# EEZ_XMOS_eval_r1B5.net
KiCad netlist of a schematic drawn in EAGLE
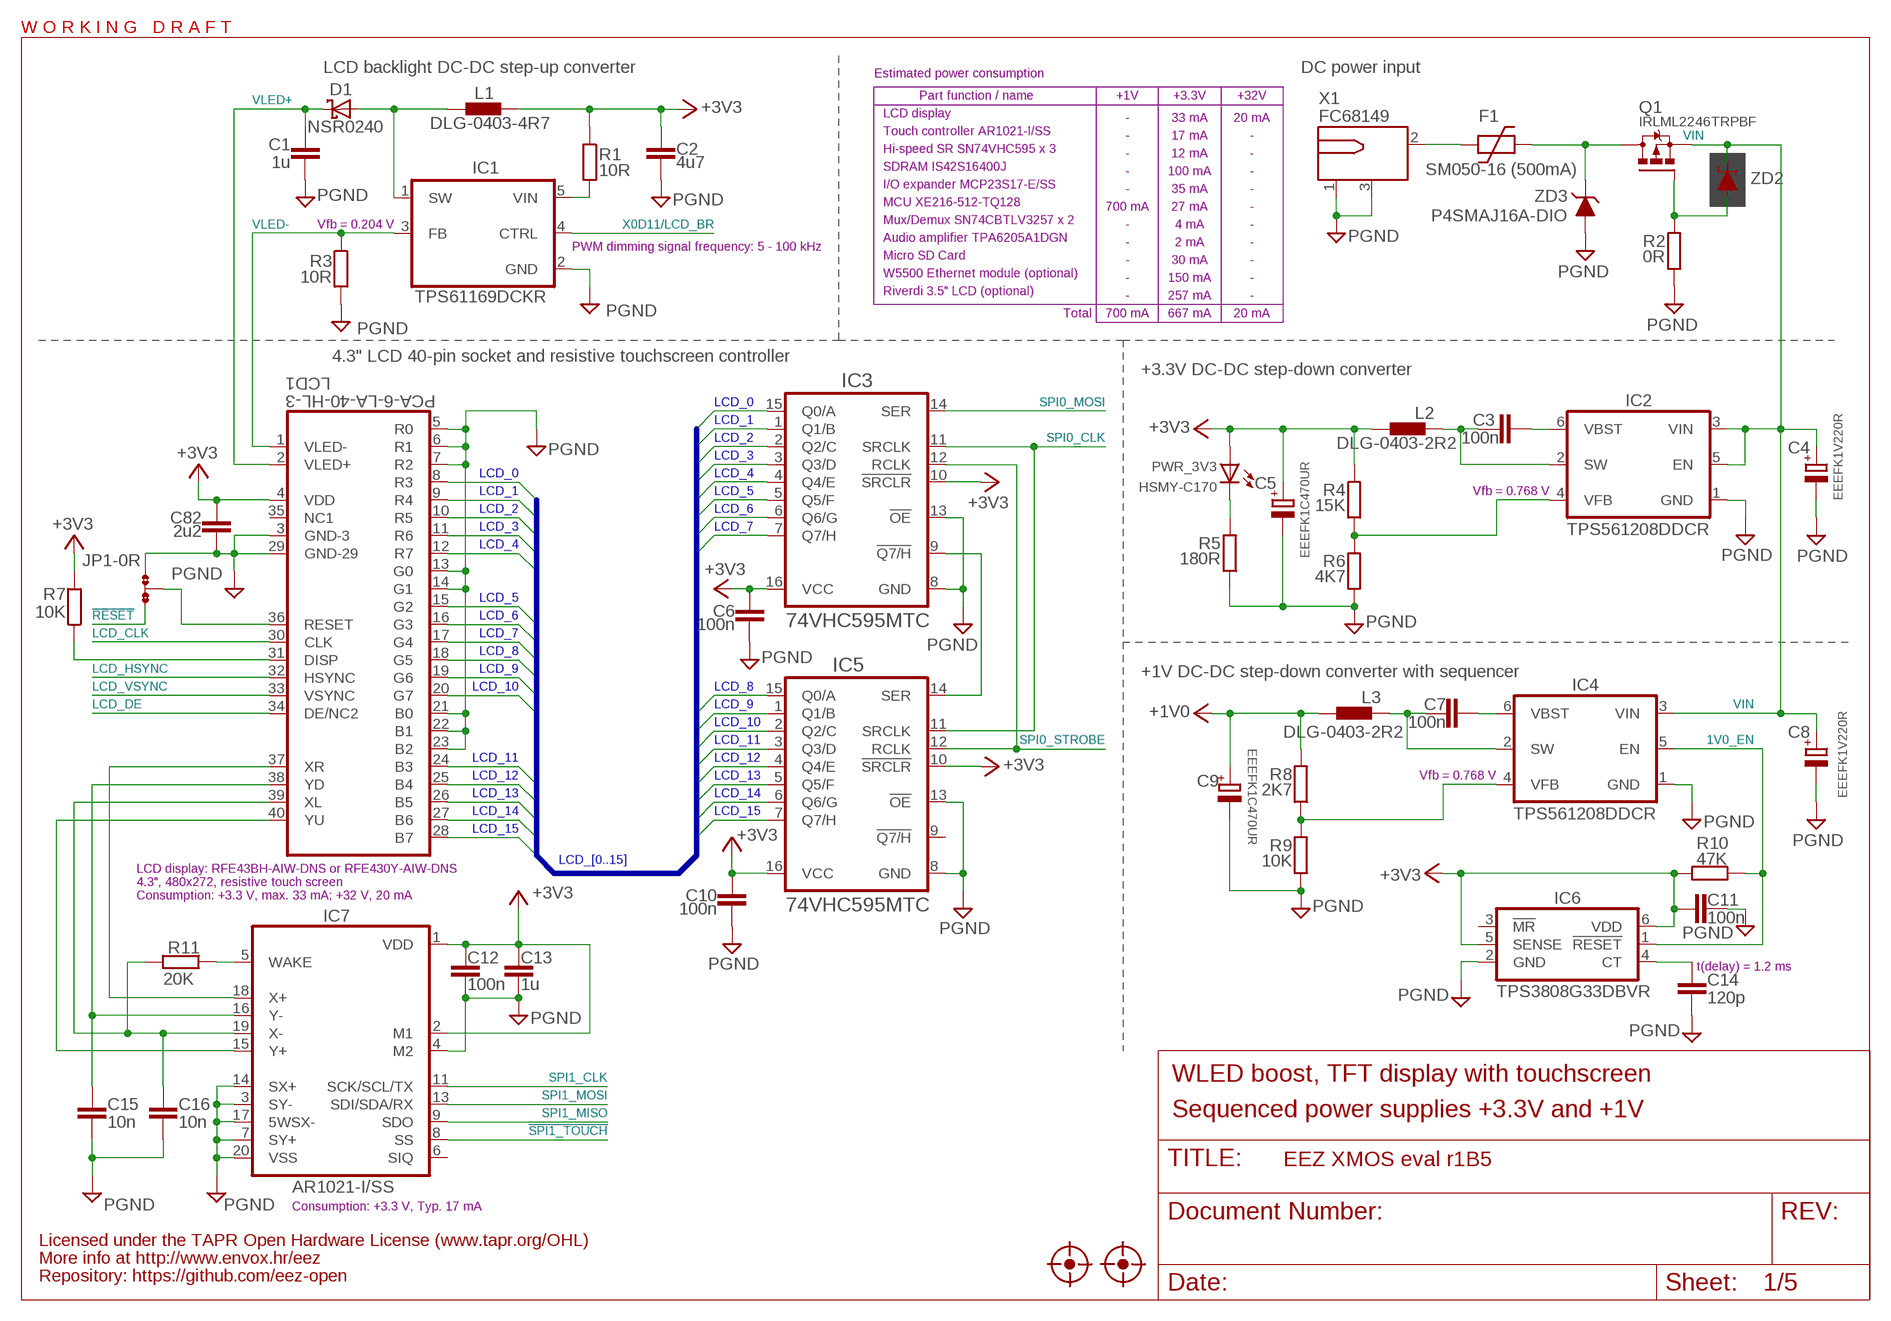
[diagram p0: schematic, sheet 1]
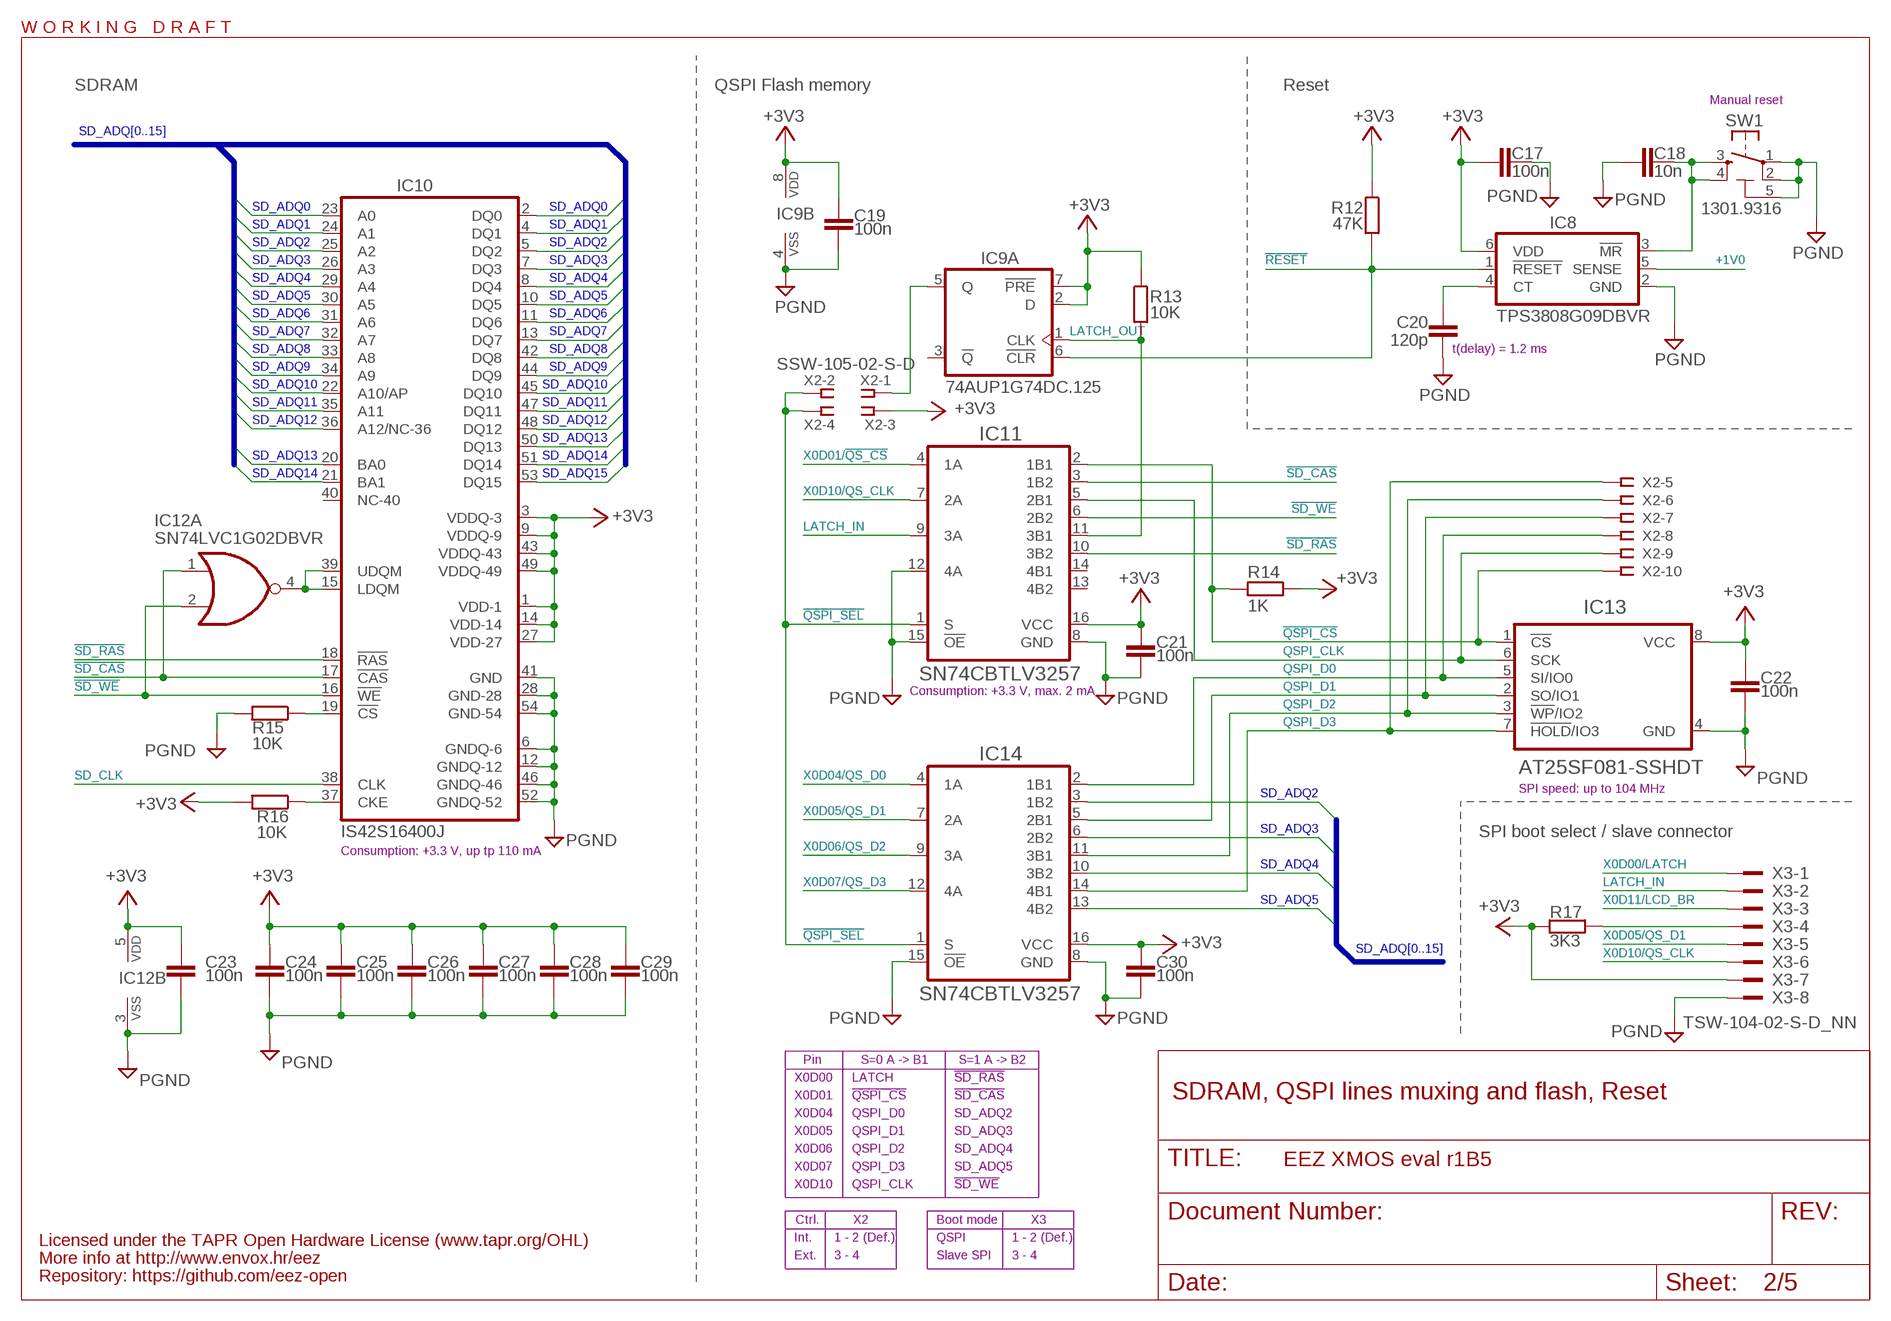
[diagram p1: schematic, sheet 2]
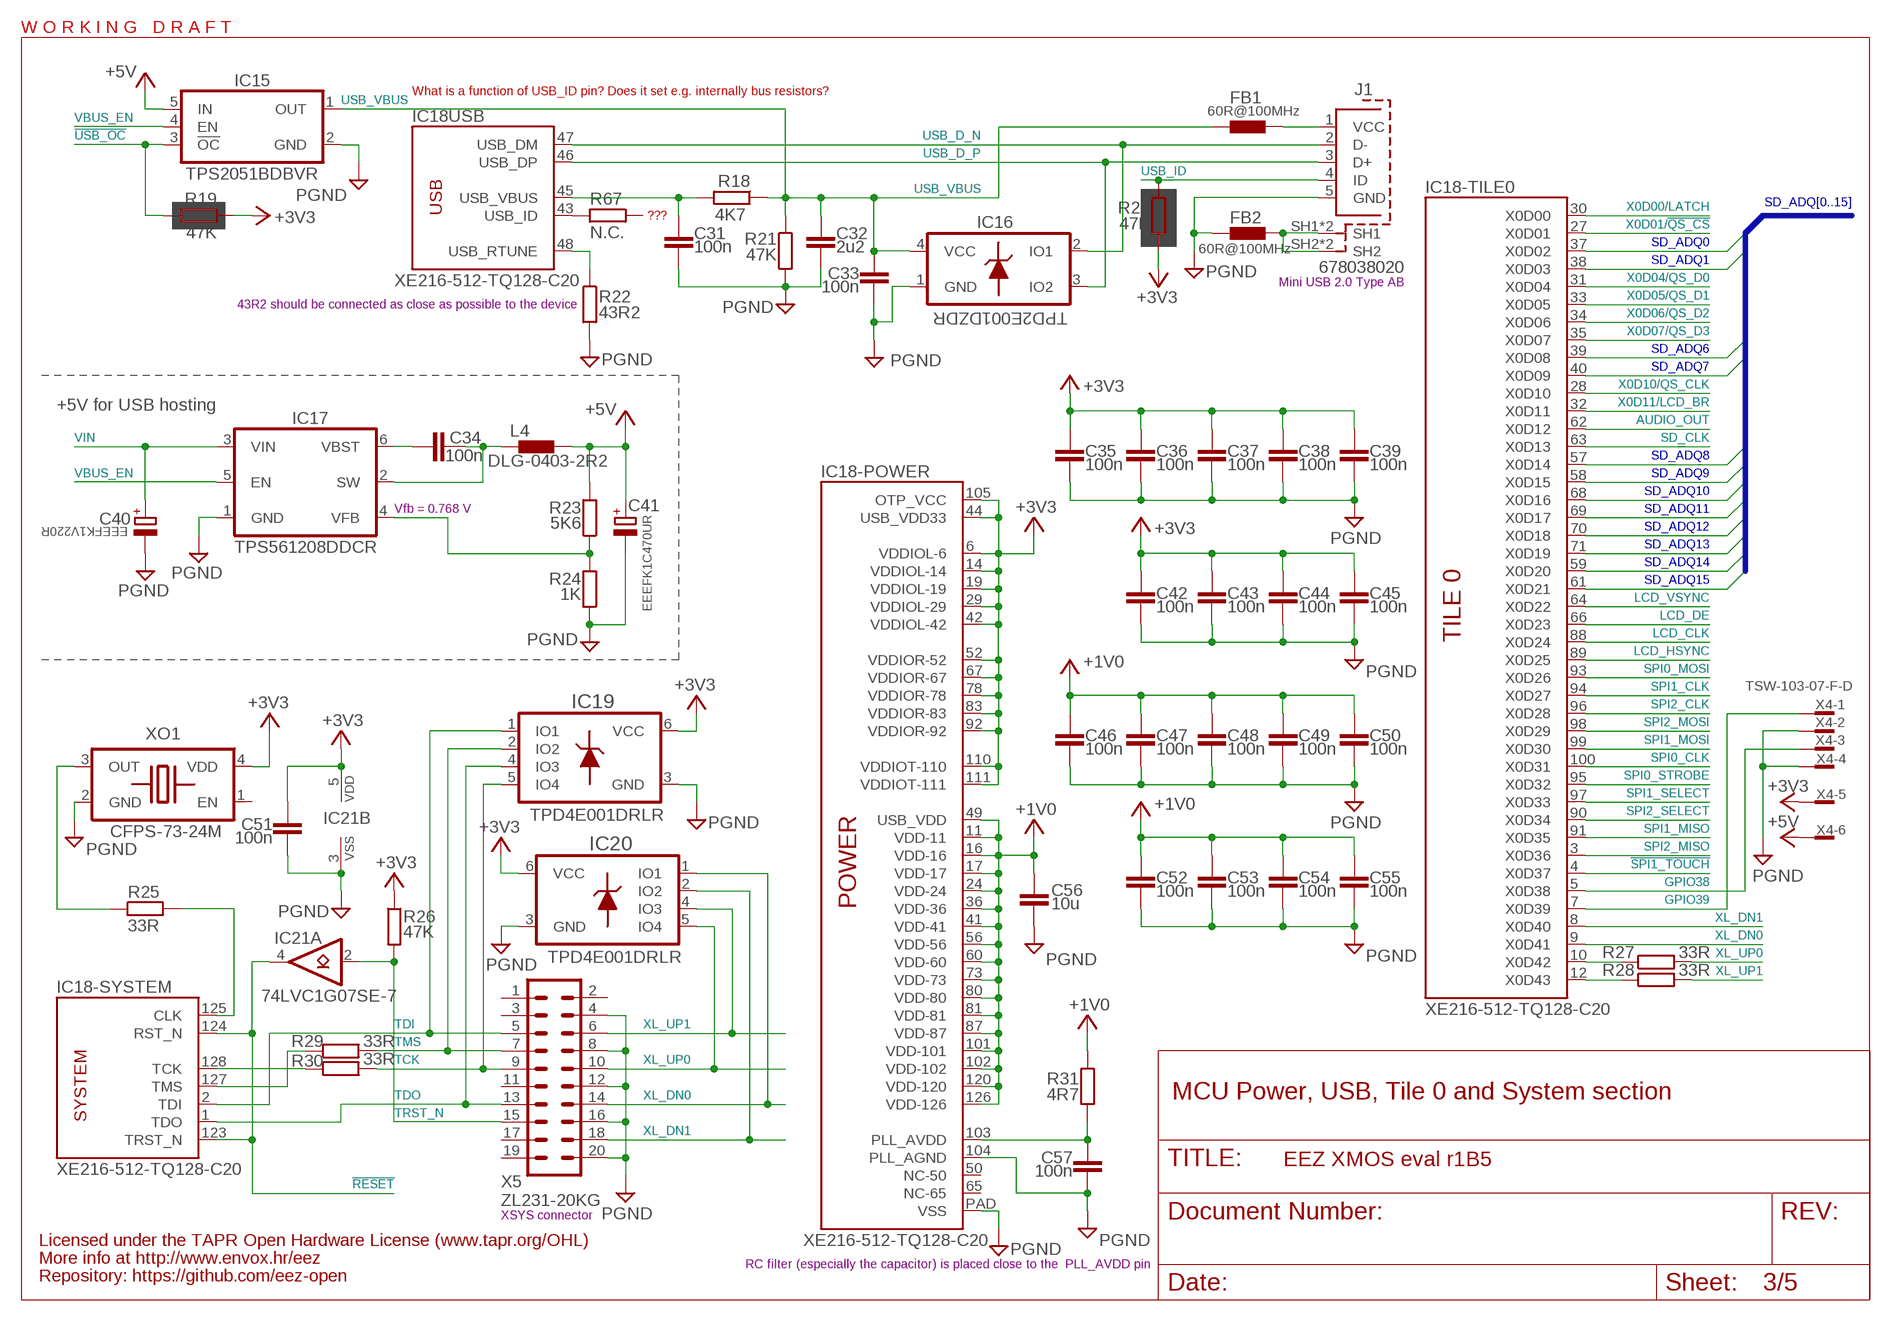
[diagram p2: schematic, sheet 3]
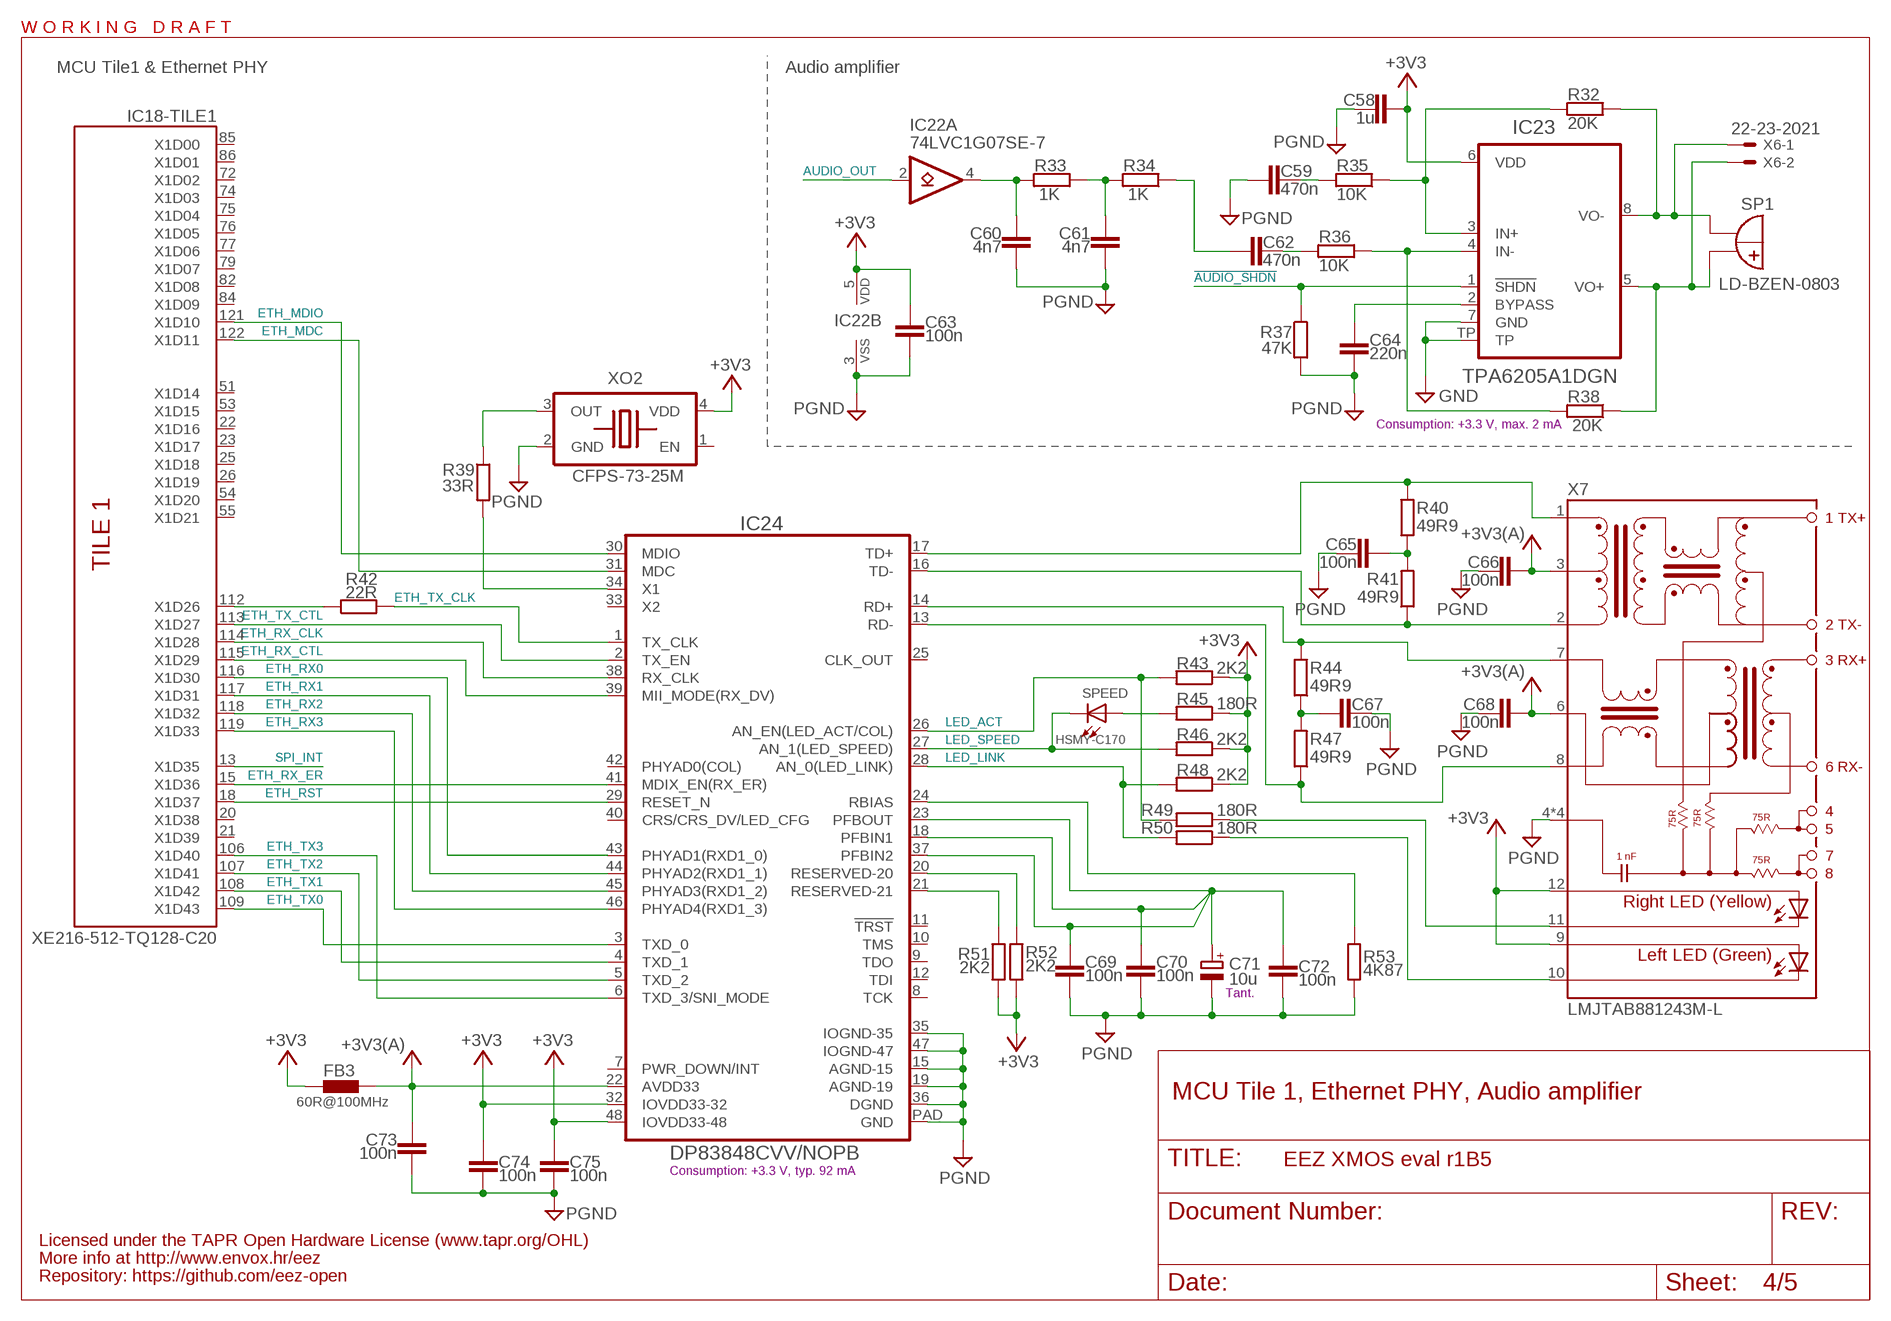
[diagram p3: schematic, sheet 4]
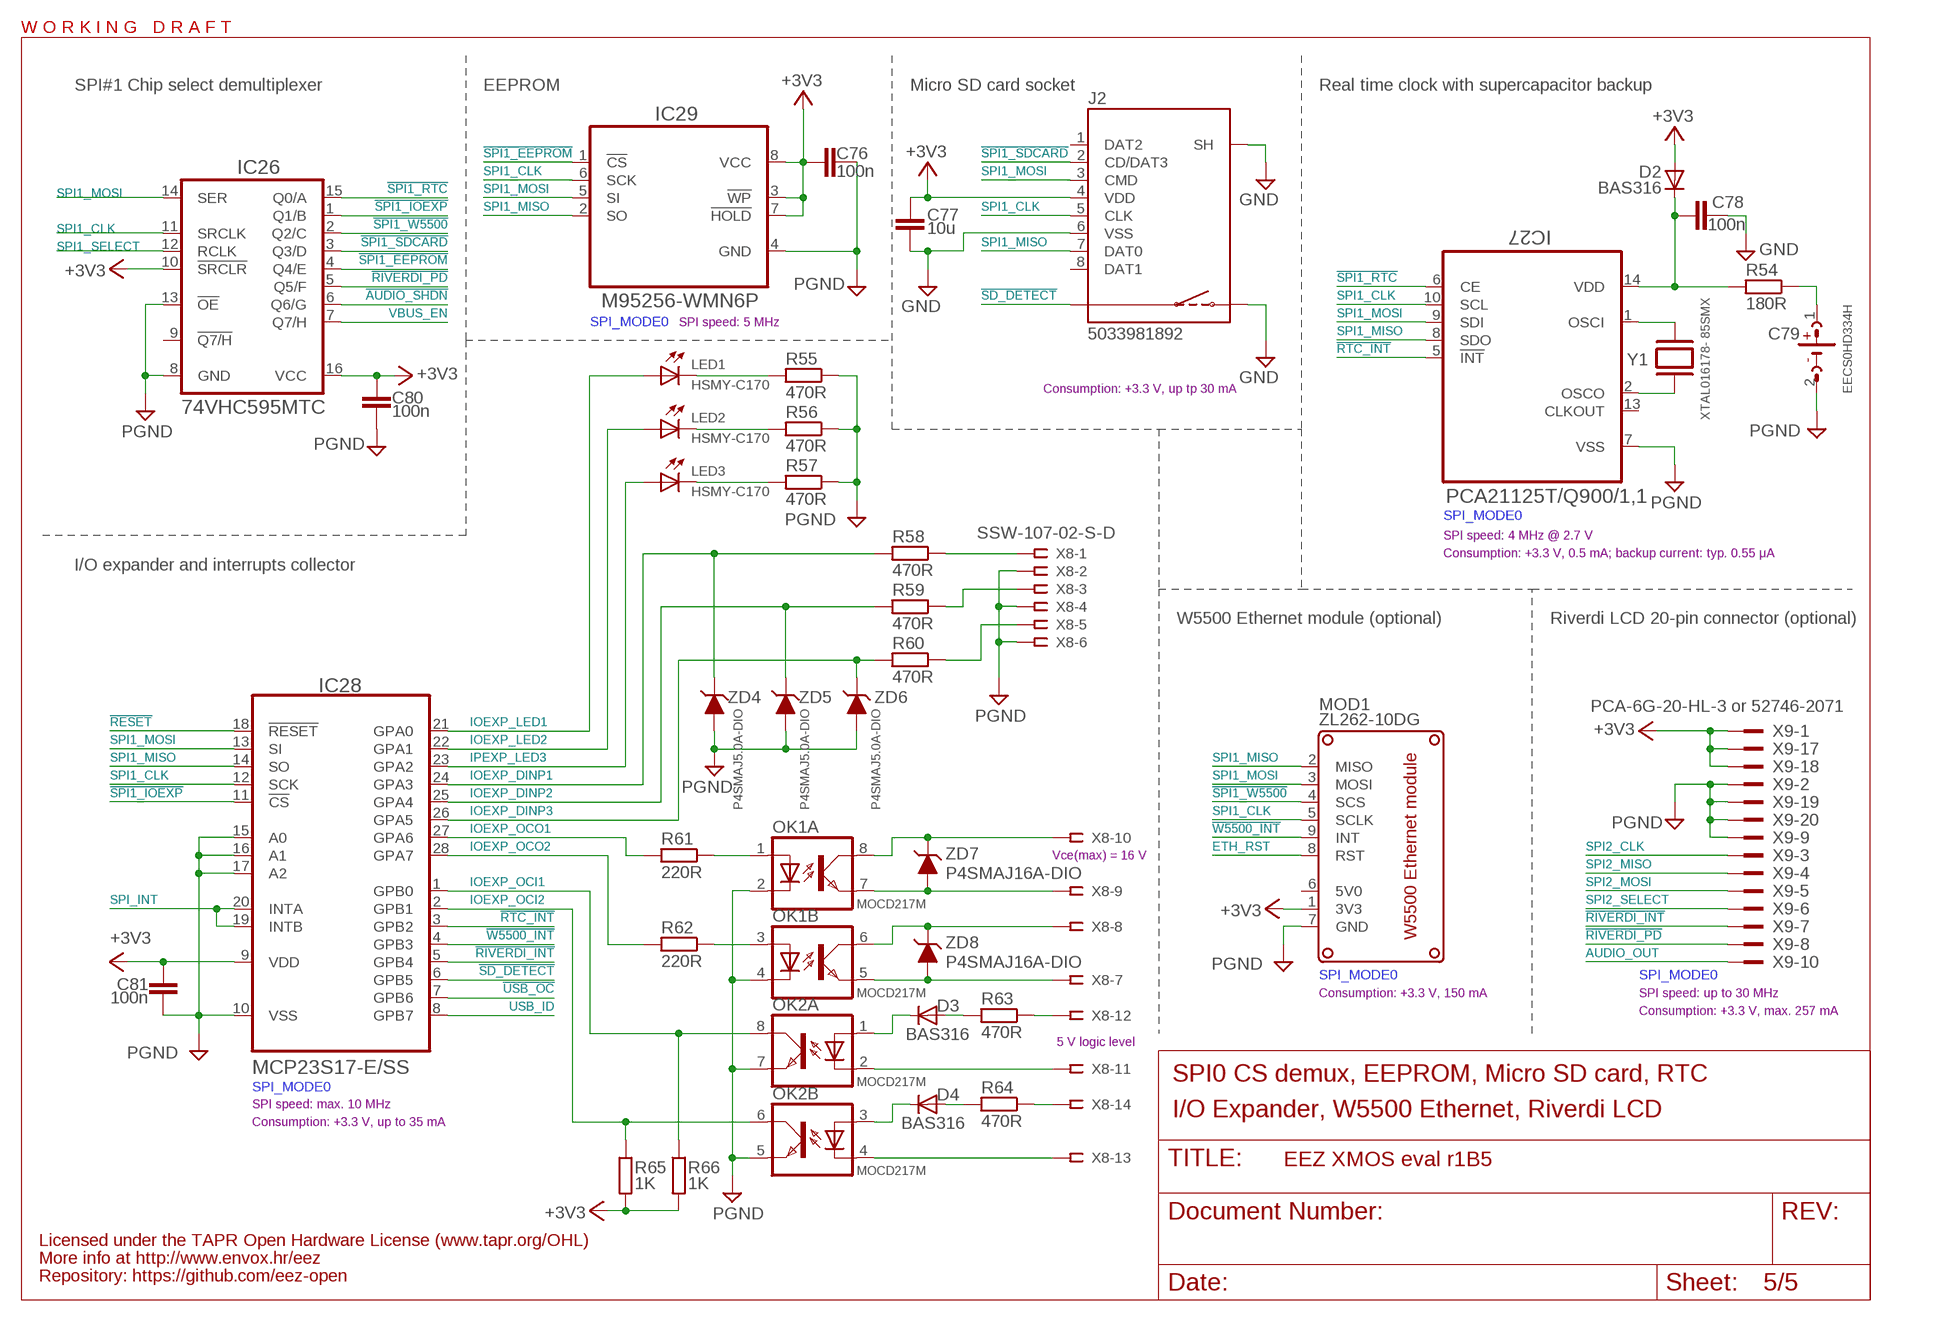
[diagram p4: schematic, sheet 5]

(export (version "E")
  (design (tool "Eeschema 10.0.6"))
  (components
    (comp (ref "C31")
      (value "100n")
      (footprint "eagle-import:C0603")
      (libsource (lib "eagle-import") (part "C-EUC0603"))
    )
    (comp (ref "C32")
      (value "2u2")
      (footprint "eagle-import:C0805")
      (libsource (lib "eagle-import") (part "C-EUC0805"))
    )
    (comp (ref "C33")
      (value "100n")
      (footprint "eagle-import:C0603")
      (libsource (lib "eagle-import") (part "C-EUC0603"))
    )
    (comp (ref "C34")
      (value "100n")
      (footprint "eagle-import:C0603")
      (libsource (lib "eagle-import") (part "C-EUC0603"))
    )
    (comp (ref "C35")
      (value "100n")
      (footprint "eagle-import:C0603")
      (libsource (lib "eagle-import") (part "C-EUC0603"))
    )
    (comp (ref "C36")
      (value "100n")
      (footprint "eagle-import:C0603")
      (libsource (lib "eagle-import") (part "C-EUC0603"))
    )
    (comp (ref "C37")
      (value "100n")
      (footprint "eagle-import:C0603")
      (libsource (lib "eagle-import") (part "C-EUC0603"))
    )
    (comp (ref "C38")
      (value "100n")
      (footprint "eagle-import:C0603")
      (libsource (lib "eagle-import") (part "C-EUC0603"))
    )
    (comp (ref "C39")
      (value "100n")
      (footprint "eagle-import:C0603")
      (libsource (lib "eagle-import") (part "C-EUC0603"))
    )
    (comp (ref "C40")
      (value "EEEFK1V220R")
      (footprint "eagle-import:CAPAE530X610N")
      (fields (field (name "MPN") "EEE-FK1V100R") (field (name "TOLERANCE") "±20 %"))
      (libsource (lib "eagle-import") (part "EEE--CASE-CFK1V100R"))
    )
    (comp (ref "C41")
      (value "EEEFK1C470UR")
      (footprint "eagle-import:CAPAE530X610N")
      (fields
        (field (name "MPN") "EEE-FK1V100R")
        (field (name "TOLERANCE") "±20 %")
        (field (name "MPN_1") "EEE-FK1V100R")
        (field (name "OC_FARNELL") "1850112  ")
        (field (name "OC_NEWARK") "23T0867")
        (field (name "PACKAGE") "CASE-C")
        (field (name "SUPPLIER") "PANASONIC")
        (field (name "TOLERANCE_1") "±20 %")
        (field (name "VOLTAGERATING") "35V")
      )
      (libsource (lib "eagle-import") (part "EEE--CASE-CFK1V100R"))
    )
    (comp (ref "C42")
      (value "100n")
      (footprint "eagle-import:C0603")
      (libsource (lib "eagle-import") (part "C-EUC0603"))
    )
    (comp (ref "C43")
      (value "100n")
      (footprint "eagle-import:C0603")
      (libsource (lib "eagle-import") (part "C-EUC0603"))
    )
    (comp (ref "C44")
      (value "100n")
      (footprint "eagle-import:C0603")
      (libsource (lib "eagle-import") (part "C-EUC0603"))
    )
    (comp (ref "C45")
      (value "100n")
      (footprint "eagle-import:C0603")
      (libsource (lib "eagle-import") (part "C-EUC0603"))
    )
    (comp (ref "C46")
      (value "100n")
      (footprint "eagle-import:C0603")
      (libsource (lib "eagle-import") (part "C-EUC0603"))
    )
    (comp (ref "C47")
      (value "100n")
      (footprint "eagle-import:C0603")
      (libsource (lib "eagle-import") (part "C-EUC0603"))
    )
    (comp (ref "C48")
      (value "100n")
      (footprint "eagle-import:C0603")
      (libsource (lib "eagle-import") (part "C-EUC0603"))
    )
    (comp (ref "C49")
      (value "100n")
      (footprint "eagle-import:C0603")
      (libsource (lib "eagle-import") (part "C-EUC0603"))
    )
    (comp (ref "C50")
      (value "100n")
      (footprint "eagle-import:C0603")
      (libsource (lib "eagle-import") (part "C-EUC0603"))
    )
    (comp (ref "C51")
      (value "100n")
      (footprint "eagle-import:C0603")
      (libsource (lib "eagle-import") (part "C-EUC0603"))
    )
    (comp (ref "C52")
      (value "100n")
      (footprint "eagle-import:C0603")
      (libsource (lib "eagle-import") (part "C-EUC0603"))
    )
    (comp (ref "C53")
      (value "100n")
      (footprint "eagle-import:C0603")
      (libsource (lib "eagle-import") (part "C-EUC0603"))
    )
    (comp (ref "C54")
      (value "100n")
      (footprint "eagle-import:C0603")
      (libsource (lib "eagle-import") (part "C-EUC0603"))
    )
    (comp (ref "C55")
      (value "100n")
      (footprint "eagle-import:C0603")
      (libsource (lib "eagle-import") (part "C-EUC0603"))
    )
    (comp (ref "C56")
      (value "10u")
      (footprint "eagle-import:C1210")
      (libsource (lib "eagle-import") (part "C-EUC1210"))
    )
    (comp (ref "C57")
      (value "100n")
      (footprint "eagle-import:C0603")
      (libsource (lib "eagle-import") (part "C-EUC0603"))
    )
    (comp (ref "FB1")
      (value "60R@100MHz")
      (footprint "eagle-import:BEAD0603")
      (libsource (lib "eagle-import") (part "FERRITE_BEAD0603"))
    )
    (comp (ref "FB2")
      (value "60R@100MHz")
      (footprint "eagle-import:BEAD0603")
      (libsource (lib "eagle-import") (part "FERRITE_BEAD0603"))
    )
    (comp (ref "IC15")
      (value "TPS2051BDBVR")
      (footprint "eagle-import:DBV5")
      (libsource (lib "eagle-import") (part "TPS2051B"))
    )
    (comp (ref "IC16")
      (value "TPD2E001DZDR")
      (footprint "eagle-import:SOP192P292X122-4N")
      (libsource (lib "eagle-import") (part "TPD2E001DZDR"))
    )
    (comp (ref "IC17")
      (value "TPS561208DDCR")
      (footprint "eagle-import:DBV6")
      (libsource (lib "eagle-import") (part "TPS56120X"))
    )
    (comp (ref "IC18")
      (value "XE216-512-TQ128-C20")
      (footprint "eagle-import:TQ128")
      (libsource (lib "eagle-import") (part "XE216-TQ128"))
    )
    (comp (ref "IC19")
      (value "TPD4E001DRLR")
      (footprint "eagle-import:DRL6")
      (libsource (lib "eagle-import") (part "TPD4E001-DRL"))
    )
    (comp (ref "IC20")
      (value "TPD4E001DRLR")
      (footprint "eagle-import:DRL6")
      (libsource (lib "eagle-import") (part "TPD4E001-DRL"))
    )
    (comp (ref "IC21")
      (value "74LVC1G07SE-7")
      (footprint "eagle-import:DCK5")
      (libsource (lib "eagle-import") (part "SN74LVC1G07-SC70"))
    )
    (comp (ref "J1")
      (value "678038020")
      (footprint "eagle-import:678038020")
      (libsource (lib "eagle-import") (part "678038020"))
    )
    (comp (ref "L4")
      (value "DLG-0403-2R2")
      (footprint "eagle-import:DE0403")
      (libsource (lib "eagle-import") (part "DE0403"))
    )
    (comp (ref "R18")
      (value "4K7")
      (footprint "eagle-import:R0805")
      (libsource (lib "eagle-import") (part "R-EU_R0805"))
    )
    (comp (ref "R19")
      (value "47K")
      (footprint "eagle-import:R0805")
      (libsource (lib "eagle-import") (part "R-EU_R0805"))
    )
    (comp (ref "R20")
      (value "47K")
      (footprint "eagle-import:R0805")
      (libsource (lib "eagle-import") (part "R-EU_R0805"))
    )
    (comp (ref "R21")
      (value "47K")
      (footprint "eagle-import:R0805")
      (libsource (lib "eagle-import") (part "R-EU_R0805"))
    )
    (comp (ref "R22")
      (value "43R2")
      (footprint "eagle-import:R0805")
      (libsource (lib "eagle-import") (part "R-EU_R0805"))
    )
    (comp (ref "R23")
      (value "5K6")
      (footprint "eagle-import:R0805")
      (libsource (lib "eagle-import") (part "R-EU_R0805"))
    )
    (comp (ref "R24")
      (value "1K")
      (footprint "eagle-import:R0805")
      (libsource (lib "eagle-import") (part "R-EU_R0805"))
    )
    (comp (ref "R25")
      (value "33R")
      (footprint "eagle-import:R0603")
      (libsource (lib "eagle-import") (part "R-EU_R0603"))
    )
    (comp (ref "R26")
      (value "47K")
      (footprint "eagle-import:R0805")
      (libsource (lib "eagle-import") (part "R-EU_R0805"))
    )
    (comp (ref "R27")
      (value "33R")
      (footprint "eagle-import:R0603")
      (libsource (lib "eagle-import") (part "R-EU_R0603"))
    )
    (comp (ref "R28")
      (value "33R")
      (footprint "eagle-import:R0603")
      (libsource (lib "eagle-import") (part "R-EU_R0603"))
    )
    (comp (ref "R29")
      (value "33R")
      (footprint "eagle-import:R0603")
      (libsource (lib "eagle-import") (part "R-EU_R0603"))
    )
    (comp (ref "R30")
      (value "33R")
      (footprint "eagle-import:R0603")
      (libsource (lib "eagle-import") (part "R-EU_R0603"))
    )
    (comp (ref "R31")
      (value "4R7")
      (footprint "eagle-import:R0805")
      (libsource (lib "eagle-import") (part "R-EU_R0805"))
    )
    (comp (ref "R67")
      (value "N.C.")
      (footprint "eagle-import:R0805")
      (libsource (lib "eagle-import") (part "R-EU_R0805"))
    )
    (comp (ref "X4")
      (value "TSW-103-07-F-D")
      (footprint "eagle-import:TSW-103-07-F-D")
      (libsource (lib "eagle-import") (part "TSW-103-07-F-D"))
    )
    (comp (ref "X5")
      (value "ZL231-20KG")
      (footprint "eagle-import:ML20L")
      (libsource (lib "eagle-import") (part "ML20L"))
    )
    (comp (ref "XO1")
      (value "CFPS-73-24M")
      (footprint "eagle-import:12SMX(C)")
      (libsource (lib "eagle-import") (part "XO-7X5MM"))
    )
    (comp (ref "C76")
      (value "100n")
      (footprint "eagle-import:C0603")
      (libsource (lib "eagle-import") (part "C-EUC0603"))
    )
    (comp (ref "C77")
      (value "10u")
      (footprint "eagle-import:C1210")
      (libsource (lib "eagle-import") (part "C-EUC1210"))
    )
    (comp (ref "C78")
      (value "100n")
      (footprint "eagle-import:C0603")
      (libsource (lib "eagle-import") (part "C-EUC0603"))
    )
    (comp (ref "C79")
      (value "EECS0HD334H")
      (footprint "eagle-import:SG-R10MM")
      (libsource (lib "eagle-import") (part "SUPER_CAP-10"))
    )
    (comp (ref "C80")
      (value "100n")
      (footprint "eagle-import:C0603")
      (libsource (lib "eagle-import") (part "C-EUC0603"))
    )
    (comp (ref "C81")
      (value "100n")
      (footprint "eagle-import:C0603")
      (libsource (lib "eagle-import") (part "C-EUC0603"))
    )
    (comp (ref "D2")
      (value "BAS316")
      (footprint "eagle-import:SOD323-W")
      (libsource (lib "eagle-import") (part "DIODE-SOD323-W"))
    )
    (comp (ref "D3")
      (value "BAS316")
      (footprint "eagle-import:SOD323-W")
      (libsource (lib "eagle-import") (part "DIODE-SOD323-W"))
    )
    (comp (ref "D4")
      (value "BAS316")
      (footprint "eagle-import:SOD323-W")
      (libsource (lib "eagle-import") (part "DIODE-SOD323-W"))
    )
    (comp (ref "IC26")
      (value "74VHC595MTC")
      (footprint "eagle-import:PW(R-PDSO-G16)")
      (libsource (lib "eagle-import") (part "SN74HC595TSSOP"))
    )
    (comp (ref "IC27")
      (value "PCA21125T/Q900/1,1")
      (footprint "eagle-import:SOP65P640X120-14N")
      (libsource (lib "eagle-import") (part "PCA21125TSSOP-14"))
    )
    (comp (ref "IC28")
      (value "MCP23S17-E/SS")
      (footprint "eagle-import:SOP65P780X200-28N")
      (libsource (lib "eagle-import") (part "MCP23S17-E/SS"))
    )
    (comp (ref "IC29")
      (value "M95256-WMN6P")
      (footprint "eagle-import:SOIC127P600X175-8N")
      (libsource (lib "eagle-import") (part "AT25XXXSOIC8"))
    )
    (comp (ref "J2")
      (value "5033981892")
      (footprint "eagle-import:5033981892")
      (libsource (lib "eagle-import") (part "5033981892"))
    )
    (comp (ref "LED1")
      (value "HSMY-C170")
      (footprint "eagle-import:LED_0805")
      (libsource (lib "eagle-import") (part "LED0805"))
    )
    (comp (ref "LED2")
      (value "HSMY-C170")
      (footprint "eagle-import:LED_0805")
      (libsource (lib "eagle-import") (part "LED0805"))
    )
    (comp (ref "LED3")
      (value "HSMY-C170")
      (footprint "eagle-import:LED_0805")
      (libsource (lib "eagle-import") (part "LED0805"))
    )
    (comp (ref "MOD1")
      (value "ZL262-10DG")
      (footprint "eagle-import:ETH_W5500_MODULE")
      (libsource (lib "eagle-import") (part "ETH_W5500_MODULE"))
    )
    (comp (ref "OK1")
      (value "MOCD217M")
      (footprint "eagle-import:SO8-OPTO")
      (libsource (lib "eagle-import") (part "MOCD217"))
    )
    (comp (ref "OK2")
      (value "MOCD217M")
      (footprint "eagle-import:SO8-OPTO")
      (libsource (lib "eagle-import") (part "MOCD217"))
    )
    (comp (ref "R54")
      (value "180R")
      (footprint "eagle-import:R0805")
      (libsource (lib "eagle-import") (part "R-EU_R0805"))
    )
    (comp (ref "R55")
      (value "470R")
      (footprint "eagle-import:R0805")
      (libsource (lib "eagle-import") (part "R-EU_R0805"))
    )
    (comp (ref "R56")
      (value "470R")
      (footprint "eagle-import:R0805")
      (libsource (lib "eagle-import") (part "R-EU_R0805"))
    )
    (comp (ref "R57")
      (value "470R")
      (footprint "eagle-import:R0805")
      (libsource (lib "eagle-import") (part "R-EU_R0805"))
    )
    (comp (ref "R58")
      (value "470R")
      (footprint "eagle-import:R0805")
      (libsource (lib "eagle-import") (part "R-EU_R0805"))
    )
    (comp (ref "R59")
      (value "470R")
      (footprint "eagle-import:R0805")
      (libsource (lib "eagle-import") (part "R-EU_R0805"))
    )
    (comp (ref "R60")
      (value "470R")
      (footprint "eagle-import:R0805")
      (libsource (lib "eagle-import") (part "R-EU_R0805"))
    )
    (comp (ref "R61")
      (value "220R")
      (footprint "eagle-import:R0805")
      (libsource (lib "eagle-import") (part "R-EU_R0805"))
    )
    (comp (ref "R62")
      (value "220R")
      (footprint "eagle-import:R0805")
      (libsource (lib "eagle-import") (part "R-EU_R0805"))
    )
    (comp (ref "R63")
      (value "470R")
      (footprint "eagle-import:R0805")
      (libsource (lib "eagle-import") (part "R-EU_R0805"))
    )
    (comp (ref "R64")
      (value "470R")
      (footprint "eagle-import:R0805")
      (libsource (lib "eagle-import") (part "R-EU_R0805"))
    )
    (comp (ref "R65")
      (value "1K")
      (footprint "eagle-import:R0805")
      (libsource (lib "eagle-import") (part "R-EU_R0805"))
    )
    (comp (ref "R66")
      (value "1K")
      (footprint "eagle-import:R0805")
      (libsource (lib "eagle-import") (part "R-EU_R0805"))
    )
    (comp (ref "X8")
      (value "SSW-107-02-S-D")
      (footprint "eagle-import:SSW-107-02-S-D")
      (libsource (lib "eagle-import") (part "SSW-107-02-S-D"))
    )
    (comp (ref "X9")
      (value "PCA-6G-20-HL-3 or 52746-2071")
      (footprint "eagle-import:FPC-20_ROTATED")
      (libsource (lib "eagle-import") (part "WR-FPC_68712014522_ROTATED"))
    )
    (comp (ref "Y1")
      (value "XTAL016178- 85SMX")
      (footprint "eagle-import:85SMX")
      (libsource (lib "eagle-import") (part "XTAL85SMX"))
    )
    (comp (ref "ZD4")
      (value "P4SMAJ5.0A-DIO")
      (footprint "eagle-import:DO214AC")
      (libsource (lib "eagle-import") (part "PSMAXX"))
    )
    (comp (ref "ZD5")
      (value "P4SMAJ5.0A-DIO")
      (footprint "eagle-import:DO214AC")
      (libsource (lib "eagle-import") (part "PSMAXX"))
    )
    (comp (ref "ZD6")
      (value "P4SMAJ5.0A-DIO")
      (footprint "eagle-import:DO214AC")
      (libsource (lib "eagle-import") (part "PSMAXX"))
    )
    (comp (ref "ZD7")
      (value "P4SMAJ16A-DIO")
      (footprint "eagle-import:DO214AC")
      (libsource (lib "eagle-import") (part "PSMAXX"))
    )
    (comp (ref "ZD8")
      (value "P4SMAJ16A-DIO")
      (footprint "eagle-import:DO214AC")
      (libsource (lib "eagle-import") (part "PSMAXX"))
    )
    (comp (ref "C58")
      (value "1u")
      (footprint "eagle-import:C0805")
      (libsource (lib "eagle-import") (part "C-EUC0805"))
    )
    (comp (ref "C59")
      (value "470n")
      (footprint "eagle-import:C0805")
      (libsource (lib "eagle-import") (part "C-EUC0805"))
    )
    (comp (ref "C60")
      (value "4n7")
      (footprint "eagle-import:C0805")
      (libsource (lib "eagle-import") (part "C-EUC0805"))
    )
    (comp (ref "C61")
      (value "4n7")
      (footprint "eagle-import:C0805")
      (libsource (lib "eagle-import") (part "C-EUC0805"))
    )
    (comp (ref "C62")
      (value "470n")
      (footprint "eagle-import:C0805")
      (libsource (lib "eagle-import") (part "C-EUC0805"))
    )
    (comp (ref "C63")
      (value "100n")
      (footprint "eagle-import:C0603")
      (libsource (lib "eagle-import") (part "C-EUC0603"))
    )
    (comp (ref "C64")
      (value "220n")
      (footprint "eagle-import:C0805")
      (libsource (lib "eagle-import") (part "C-EUC0805"))
    )
    (comp (ref "C65")
      (value "100n")
      (footprint "eagle-import:C0603")
      (libsource (lib "eagle-import") (part "C-EUC0603"))
    )
    (comp (ref "C66")
      (value "100n")
      (footprint "eagle-import:C0603")
      (libsource (lib "eagle-import") (part "C-EUC0603"))
    )
    (comp (ref "C67")
      (value "100n")
      (footprint "eagle-import:C0603")
      (libsource (lib "eagle-import") (part "C-EUC0603"))
    )
    (comp (ref "C68")
      (value "100n")
      (footprint "eagle-import:C0603")
      (libsource (lib "eagle-import") (part "C-EUC0603"))
    )
    (comp (ref "C69")
      (value "100n")
      (footprint "eagle-import:C0603")
      (libsource (lib "eagle-import") (part "C-EUC0603"))
    )
    (comp (ref "C70")
      (value "100n")
      (footprint "eagle-import:C0603")
      (libsource (lib "eagle-import") (part "C-EUC0603"))
    )
    (comp (ref "C71")
      (value "10u")
      (footprint "eagle-import:EC1206")
      (libsource (lib "eagle-import") (part "ECAP1206"))
    )
    (comp (ref "C72")
      (value "100n")
      (footprint "eagle-import:C0603")
      (libsource (lib "eagle-import") (part "C-EUC0603"))
    )
    (comp (ref "C73")
      (value "100n")
      (footprint "eagle-import:C0603")
      (libsource (lib "eagle-import") (part "C-EUC0603"))
    )
    (comp (ref "C74")
      (value "100n")
      (footprint "eagle-import:C0603")
      (libsource (lib "eagle-import") (part "C-EUC0603"))
    )
    (comp (ref "C75")
      (value "100n")
      (footprint "eagle-import:C0603")
      (libsource (lib "eagle-import") (part "C-EUC0603"))
    )
    (comp (ref "FB3")
      (value "60R@100MHz")
      (footprint "eagle-import:BEAD0603")
      (libsource (lib "eagle-import") (part "FERRITE_BEAD0603"))
    )
    (comp (ref "IC22")
      (value "74LVC1G07SE-7")
      (footprint "eagle-import:DCK5")
      (libsource (lib "eagle-import") (part "SN74LVC1G07-SC70"))
    )
    (comp (ref "IC23")
      (value "TPA6205A1DGN")
      (footprint "eagle-import:SOP65P490X110-9N")
      (libsource (lib "eagle-import") (part "TPA6205"))
    )
    (comp (ref "IC24")
      (value "DP83848CVV/NOPB")
      (footprint "eagle-import:PT48+PAD")
      (libsource (lib "eagle-import") (part "DP83848"))
    )
    (comp (ref "R32")
      (value "20K")
      (footprint "eagle-import:R0805")
      (libsource (lib "eagle-import") (part "R-EU_R0805"))
    )
    (comp (ref "R33")
      (value "1K")
      (footprint "eagle-import:R0805")
      (libsource (lib "eagle-import") (part "R-EU_R0805"))
    )
    (comp (ref "R34")
      (value "1K")
      (footprint "eagle-import:R0805")
      (libsource (lib "eagle-import") (part "R-EU_R0805"))
    )
    (comp (ref "R35")
      (value "10K")
      (footprint "eagle-import:R0805")
      (libsource (lib "eagle-import") (part "R-EU_R0805"))
    )
    (comp (ref "R36")
      (value "10K")
      (footprint "eagle-import:R0805")
      (libsource (lib "eagle-import") (part "R-EU_R0805"))
    )
    (comp (ref "R37")
      (value "47K")
      (footprint "eagle-import:R0805")
      (libsource (lib "eagle-import") (part "R-EU_R0805"))
    )
    (comp (ref "R38")
      (value "20K")
      (footprint "eagle-import:R0805")
      (libsource (lib "eagle-import") (part "R-EU_R0805"))
    )
    (comp (ref "R39")
      (value "33R")
      (footprint "eagle-import:R0603")
      (libsource (lib "eagle-import") (part "R-EU_R0603"))
    )
    (comp (ref "R40")
      (value "49R9")
      (footprint "eagle-import:R0805")
      (libsource (lib "eagle-import") (part "R-EU_R0805"))
    )
    (comp (ref "R41")
      (value "49R9")
      (footprint "eagle-import:R0805")
      (libsource (lib "eagle-import") (part "R-EU_R0805"))
    )
    (comp (ref "R42")
      (value "22R")
      (footprint "eagle-import:R0805")
      (libsource (lib "eagle-import") (part "R-EU_R0805"))
    )
    (comp (ref "R43")
      (value "2K2")
      (footprint "eagle-import:R0805")
      (libsource (lib "eagle-import") (part "R-EU_R0805"))
    )
    (comp (ref "R44")
      (value "49R9")
      (footprint "eagle-import:R0805")
      (libsource (lib "eagle-import") (part "R-EU_R0805"))
    )
    (comp (ref "R45")
      (value "180R")
      (footprint "eagle-import:R0805")
      (libsource (lib "eagle-import") (part "R-EU_R0805"))
    )
    (comp (ref "R46")
      (value "2K2")
      (footprint "eagle-import:R0805")
      (libsource (lib "eagle-import") (part "R-EU_R0805"))
    )
    (comp (ref "R47")
      (value "49R9")
      (footprint "eagle-import:R0805")
      (libsource (lib "eagle-import") (part "R-EU_R0805"))
    )
    (comp (ref "R48")
      (value "2K2")
      (footprint "eagle-import:R0805")
      (libsource (lib "eagle-import") (part "R-EU_R0805"))
    )
    (comp (ref "R49")
      (value "180R")
      (footprint "eagle-import:R0805")
      (libsource (lib "eagle-import") (part "R-EU_R0805"))
    )
    (comp (ref "R50")
      (value "180R")
      (footprint "eagle-import:R0805")
      (libsource (lib "eagle-import") (part "R-EU_R0805"))
    )
    (comp (ref "R51")
      (value "2K2")
      (footprint "eagle-import:R0805")
      (libsource (lib "eagle-import") (part "R-EU_R0805"))
    )
    (comp (ref "R52")
      (value "2K2")
      (footprint "eagle-import:R0805")
      (libsource (lib "eagle-import") (part "R-EU_R0805"))
    )
    (comp (ref "R53")
      (value "4K87")
      (footprint "eagle-import:R0603")
      (libsource (lib "eagle-import") (part "R-EU_R0603"))
    )
    (comp (ref "SP1")
      (value "LD-BZEN-0803")
      (footprint "eagle-import:LD-BZEN-0803")
      (libsource (lib "eagle-import") (part "BUZZER-0803"))
    )
    (comp (ref "SPEED")
      (value "HSMY-C170")
      (footprint "eagle-import:LED_0805")
      (libsource (lib "eagle-import") (part "LED0805"))
    )
    (comp (ref "X6")
      (value "22-23-2021")
      (footprint "eagle-import:22-23-2021")
      (fields
        (field (name "MF") "MOLEX")
        (field (name "MPN") "22-23-2021")
        (field (name "OC_FARNELL") "1462926")
        (field (name "OC_NEWARK") "25C3832")
      )
      (libsource (lib "eagle-import") (part "22-23-2021"))
    )
    (comp (ref "X7")
      (value "LMJTAB881243M-L")
      (footprint "eagle-import:RJ45-TRAFO-LED")
      (libsource (lib "eagle-import") (part "RJ45-TRAFO-LED"))
    )
    (comp (ref "XO2")
      (value "CFPS-73-25M")
      (footprint "eagle-import:12SMX(C)")
      (libsource (lib "eagle-import") (part "XO-7X5MM"))
    )
    (comp (ref "C1")
      (value "1u")
      (footprint "eagle-import:C0805")
      (libsource (lib "eagle-import") (part "C-EUC0805"))
    )
    (comp (ref "C2")
      (value "4u7")
      (footprint "eagle-import:C1206")
      (libsource (lib "eagle-import") (part "C-EUC1206"))
    )
    (comp (ref "C3")
      (value "100n")
      (footprint "eagle-import:C0603")
      (libsource (lib "eagle-import") (part "C-EUC0603"))
    )
    (comp (ref "C4")
      (value "EEEFK1V220R")
      (footprint "eagle-import:CAPAE530X610N")
      (fields (field (name "MPN") "EEE-FK1V100R") (field (name "TOLERANCE") "±20 %"))
      (libsource (lib "eagle-import") (part "EEE--CASE-CFK1V100R"))
    )
    (comp (ref "C5")
      (value "EEEFK1C470UR")
      (footprint "eagle-import:CAPAE530X610N")
      (fields
        (field (name "MPN") "EEE-FK1V100R")
        (field (name "TOLERANCE") "±20 %")
        (field (name "MPN_1") "EEE-FK1V100R")
        (field (name "OC_FARNELL") "1850112  ")
        (field (name "OC_NEWARK") "23T0867")
        (field (name "PACKAGE") "CASE-C")
        (field (name "SUPPLIER") "PANASONIC")
        (field (name "TOLERANCE_1") "±20 %")
        (field (name "VOLTAGERATING") "35V")
      )
      (libsource (lib "eagle-import") (part "EEE--CASE-CFK1V100R"))
    )
    (comp (ref "C6")
      (value "100n")
      (footprint "eagle-import:C0603")
      (libsource (lib "eagle-import") (part "C-EUC0603"))
    )
    (comp (ref "C7")
      (value "100n")
      (footprint "eagle-import:C0603")
      (libsource (lib "eagle-import") (part "C-EUC0603"))
    )
    (comp (ref "C8")
      (value "EEEFK1V220R")
      (footprint "eagle-import:CAPAE530X610N")
      (fields
        (field (name "MPN") "EEE-FK1V100R")
        (field (name "TOLERANCE") "±20 %")
        (field (name "MPN_1") "EEE-FK1V100R")
        (field (name "OC_FARNELL") "1850112  ")
        (field (name "OC_NEWARK") "23T0867")
        (field (name "PACKAGE") "CASE-C")
        (field (name "SUPPLIER") "PANASONIC")
        (field (name "TOLERANCE_1") "±20 %")
        (field (name "VOLTAGERATING") "35V")
      )
      (libsource (lib "eagle-import") (part "EEE--CASE-CFK1V100R"))
    )
    (comp (ref "C9")
      (value "EEEFK1C470UR")
      (footprint "eagle-import:CAPAE530X610N")
      (fields
        (field (name "MPN") "EEE-FK1V100R")
        (field (name "TOLERANCE") "±20 %")
        (field (name "MPN_1") "EEE-FK1V100R")
        (field (name "OC_FARNELL") "1850112  ")
        (field (name "OC_NEWARK") "23T0867")
        (field (name "PACKAGE") "CASE-C")
        (field (name "SUPPLIER") "PANASONIC")
        (field (name "TOLERANCE_1") "±20 %")
        (field (name "VOLTAGERATING") "35V")
      )
      (libsource (lib "eagle-import") (part "EEE--CASE-CFK1V100R"))
    )
    (comp (ref "C10")
      (value "100n")
      (footprint "eagle-import:C0603")
      (libsource (lib "eagle-import") (part "C-EUC0603"))
    )
    (comp (ref "C11")
      (value "100n")
      (footprint "eagle-import:C0603")
      (libsource (lib "eagle-import") (part "C-EUC0603"))
    )
    (comp (ref "C12")
      (value "100n")
      (footprint "eagle-import:C0603")
      (libsource (lib "eagle-import") (part "C-EUC0603"))
    )
    (comp (ref "C13")
      (value "1u")
      (footprint "eagle-import:C0805")
      (libsource (lib "eagle-import") (part "C-EUC0805"))
    )
    (comp (ref "C14")
      (value "120p")
      (footprint "eagle-import:C0805")
      (libsource (lib "eagle-import") (part "C-EUC0805"))
    )
    (comp (ref "C15")
      (value "10n")
      (footprint "eagle-import:C0805")
      (libsource (lib "eagle-import") (part "C-EUC0805"))
    )
    (comp (ref "C16")
      (value "10n")
      (footprint "eagle-import:C0805")
      (libsource (lib "eagle-import") (part "C-EUC0805"))
    )
    (comp (ref "C82")
      (value "2u2")
      (footprint "eagle-import:C0805")
      (libsource (lib "eagle-import") (part "C-EUC0805"))
    )
    (comp (ref "D1")
      (value "NSR0240")
      (footprint "eagle-import:SOD123")
      (libsource (lib "eagle-import") (part "SCHOTTKYSOD123"))
    )
    (comp (ref "F1")
      (value "SM050-16 (500mA)")
      (footprint "eagle-import:F1210")
      (libsource (lib "eagle-import") (part "FUSE_RESETTABLE21210"))
    )
    (comp (ref "FM1")
      (value "FIDUCIAL_2")
      (footprint "eagle-import:FIDUCIAL_DUAL")
      (libsource (lib "eagle-import") (part "FIDUCIAL_2"))
    )
    (comp (ref "FM2")
      (value "FIDUCIAL_2")
      (footprint "eagle-import:FIDUCIAL_DUAL")
      (libsource (lib "eagle-import") (part "FIDUCIAL_2"))
    )
    (comp (ref "IC1")
      (value "TPS61169DCKR")
      (footprint "eagle-import:DCK0005A_N")
      (fields (field (name "MANUFACTURER") "Texas Instruments"))
      (libsource (lib "eagle-import") (part "TPS61169DCKR"))
    )
    (comp (ref "IC2")
      (value "TPS561208DDCR")
      (footprint "eagle-import:DBV6")
      (libsource (lib "eagle-import") (part "TPS56120X"))
    )
    (comp (ref "IC3")
      (value "74VHC595MTC")
      (footprint "eagle-import:PW(R-PDSO-G16)")
      (libsource (lib "eagle-import") (part "SN74HC595TSSOP"))
    )
    (comp (ref "IC4")
      (value "TPS561208DDCR")
      (footprint "eagle-import:DBV6")
      (libsource (lib "eagle-import") (part "TPS56120X"))
    )
    (comp (ref "IC5")
      (value "74VHC595MTC")
      (footprint "eagle-import:PW(R-PDSO-G16)")
      (libsource (lib "eagle-import") (part "SN74HC595TSSOP"))
    )
    (comp (ref "IC6")
      (value "TPS3808G33DBVR")
      (footprint "eagle-import:DBV6")
      (fields
        (field (name "GENERIC_PART_NUMBER") "TPS3808G01")
        (field (name "MANUFACTURER") "Texas Instruments")
        (field (name "MANUFACTURER_PART_NUMBER") "tps3808g01_dbv_6")
      )
      (libsource (lib "eagle-import") (part "TPS3808"))
    )
    (comp (ref "IC7")
      (value "AR1021-I/SS")
      (footprint "eagle-import:SOP65P780X200-20N")
      (libsource (lib "eagle-import") (part "AR1021-I/SS"))
    )
    (comp (ref "JP1")
      (value "0R-JUMPA")
      (footprint "eagle-import:A0R-JMP")
      (libsource (lib "eagle-import") (part "0R-JUMPA"))
    )
    (comp (ref "L1")
      (value "DLG-0403-4R7")
      (footprint "eagle-import:DE0403")
      (libsource (lib "eagle-import") (part "DE0403"))
    )
    (comp (ref "L2")
      (value "DLG-0403-2R2")
      (footprint "eagle-import:DE0403")
      (libsource (lib "eagle-import") (part "DE0403"))
    )
    (comp (ref "L3")
      (value "DLG-0403-2R2")
      (footprint "eagle-import:DE0403")
      (libsource (lib "eagle-import") (part "DE0403"))
    )
    (comp (ref "LCD1")
      (value "PCA-6-LA-40-HL-3")
      (footprint "eagle-import:FPC_40")
      (libsource (lib "eagle-import") (part "RFE430Y-AIW-DNS"))
    )
    (comp (ref "PWR_3V3")
      (value "HSMY-C170")
      (footprint "eagle-import:LED_0805")
      (libsource (lib "eagle-import") (part "LED0805"))
    )
    (comp (ref "Q1")
      (value "IRLML2246TRPBF")
      (footprint "eagle-import:SOT95P237X112-3N")
      (libsource (lib "eagle-import") (part "IRLML2246TRPBF"))
    )
    (comp (ref "R1")
      (value "10R")
      (footprint "eagle-import:R1206")
      (libsource (lib "eagle-import") (part "R-EU_R1206"))
    )
    (comp (ref "R2")
      (value "0R")
      (footprint "eagle-import:R0805")
      (libsource (lib "eagle-import") (part "R-EU_R0805"))
    )
    (comp (ref "R3")
      (value "10R")
      (footprint "eagle-import:R1206")
      (libsource (lib "eagle-import") (part "R-EU_R1206"))
    )
    (comp (ref "R4")
      (value "15K")
      (footprint "eagle-import:R0805")
      (libsource (lib "eagle-import") (part "R-EU_R0805"))
    )
    (comp (ref "R5")
      (value "180R")
      (footprint "eagle-import:R0805")
      (libsource (lib "eagle-import") (part "R-EU_R0805"))
    )
    (comp (ref "R6")
      (value "4K7")
      (footprint "eagle-import:R0805")
      (libsource (lib "eagle-import") (part "R-EU_R0805"))
    )
    (comp (ref "R7")
      (value "10K")
      (footprint "eagle-import:R0805")
      (libsource (lib "eagle-import") (part "R-EU_R0805"))
    )
    (comp (ref "R8")
      (value "2K7")
      (footprint "eagle-import:R0805")
      (libsource (lib "eagle-import") (part "R-EU_R0805"))
    )
    (comp (ref "R9")
      (value "10K")
      (footprint "eagle-import:R0805")
      (libsource (lib "eagle-import") (part "R-EU_R0805"))
    )
    (comp (ref "R10")
      (value "47K")
      (footprint "eagle-import:R0805")
      (libsource (lib "eagle-import") (part "R-EU_R0805"))
    )
    (comp (ref "R11")
      (value "20K")
      (footprint "eagle-import:R0805")
      (libsource (lib "eagle-import") (part "R-EU_R0805"))
    )
    (comp (ref "X1")
      (value "FC68149")
      (footprint "eagle-import:DC-21MM")
      (libsource (lib "eagle-import") (part "DC21_PWRX"))
    )
    (comp (ref "ZD2")
      (value "ZENER-DIODESOD323")
      (footprint "eagle-import:SOD323-W")
      (libsource (lib "eagle-import") (part "ZENER-DIODESOD323"))
    )
    (comp (ref "ZD3")
      (value "P4SMAJ16A-DIO")
      (footprint "eagle-import:DO214AC")
      (libsource (lib "eagle-import") (part "PSMAXX"))
    )
    (comp (ref "C17")
      (value "100n")
      (footprint "eagle-import:C0603")
      (libsource (lib "eagle-import") (part "C-EUC0603"))
    )
    (comp (ref "C18")
      (value "10n")
      (footprint "eagle-import:C0805")
      (libsource (lib "eagle-import") (part "C-EUC0805"))
    )
    (comp (ref "C19")
      (value "100n")
      (footprint "eagle-import:C0603")
      (libsource (lib "eagle-import") (part "C-EUC0603"))
    )
    (comp (ref "C20")
      (value "120p")
      (footprint "eagle-import:C0805")
      (libsource (lib "eagle-import") (part "C-EUC0805"))
    )
    (comp (ref "C21")
      (value "100n")
      (footprint "eagle-import:C0603")
      (libsource (lib "eagle-import") (part "C-EUC0603"))
    )
    (comp (ref "C22")
      (value "100n")
      (footprint "eagle-import:C0603")
      (libsource (lib "eagle-import") (part "C-EUC0603"))
    )
    (comp (ref "C23")
      (value "100n")
      (footprint "eagle-import:C0603")
      (libsource (lib "eagle-import") (part "C-EUC0603"))
    )
    (comp (ref "C24")
      (value "100n")
      (footprint "eagle-import:C0603")
      (libsource (lib "eagle-import") (part "C-EUC0603"))
    )
    (comp (ref "C25")
      (value "100n")
      (footprint "eagle-import:C0603")
      (libsource (lib "eagle-import") (part "C-EUC0603"))
    )
    (comp (ref "C26")
      (value "100n")
      (footprint "eagle-import:C0603")
      (libsource (lib "eagle-import") (part "C-EUC0603"))
    )
    (comp (ref "C27")
      (value "100n")
      (footprint "eagle-import:C0603")
      (libsource (lib "eagle-import") (part "C-EUC0603"))
    )
    (comp (ref "C28")
      (value "100n")
      (footprint "eagle-import:C0603")
      (libsource (lib "eagle-import") (part "C-EUC0603"))
    )
    (comp (ref "C29")
      (value "100n")
      (footprint "eagle-import:C0603")
      (libsource (lib "eagle-import") (part "C-EUC0603"))
    )
    (comp (ref "C30")
      (value "100n")
      (footprint "eagle-import:C0603")
      (libsource (lib "eagle-import") (part "C-EUC0603"))
    )
    (comp (ref "IC8")
      (value "TPS3808G09DBVR")
      (footprint "eagle-import:DBV6")
      (fields
        (field (name "GENERIC_PART_NUMBER") "TPS3808G01")
        (field (name "MANUFACTURER") "Texas Instruments")
        (field (name "MANUFACTURER_PART_NUMBER") "tps3808g01_dbv_6")
        (field (name "DATASHEETURL") "httpwww.ti.comlitgpnTPS3808G01")
        (field (name "FAMILY_NAME") "SUPERVISOR AND RESET IC")
        (field (name "GENERIC_PART_NUMBER_1") "TPS3808G01")
        (field (name "INDUSTRY_STD_PKG_TYPE") "SOT23")
        (field (name "MANUFACTURER_1") "Texas Instruments")
        (field (name "MANUFACTURER_PART_NUMBER_1") "tps3808g01_dbv_6")
        (field (name "PACKAGE_DESIGNATOR") "DBV")
        (field (name "PIN_COUNT") "6")
        (field (name "VENDOR") "Texas Instruments")
      )
      (libsource (lib "eagle-import") (part "TPS3808"))
    )
    (comp (ref "IC9")
      (value "74AUP1G74DC.125")
      (footprint "eagle-import:DCU8")
      (libsource (lib "eagle-import") (part "SN74LVC1G74DCTR-VSSOP"))
    )
    (comp (ref "IC10")
      (value "IS42S16400J")
      (footprint "eagle-import:TSOPII-54")
      (libsource (lib "eagle-import") (part "IS42S16400"))
    )
    (comp (ref "IC11")
      (value "SN74CBTLV3257")
      (footprint "eagle-import:PW(R-PDSO-G16)")
      (libsource (lib "eagle-import") (part "SN74CBTLV3257"))
    )
    (comp (ref "IC12")
      (value "SN74LVC1G02DBVR")
      (footprint "eagle-import:DBV5")
      (libsource (lib "eagle-import") (part "SN74LVC1G02DBVR"))
    )
    (comp (ref "IC13")
      (value "AT25SF081-SSHDT")
      (footprint "eagle-import:SOIC127P600X175-8N")
      (libsource (lib "eagle-import") (part "AT25SFXXX"))
    )
    (comp (ref "IC14")
      (value "SN74CBTLV3257")
      (footprint "eagle-import:PW(R-PDSO-G16)")
      (libsource (lib "eagle-import") (part "SN74CBTLV3257"))
    )
    (comp (ref "R12")
      (value "47K")
      (footprint "eagle-import:R0805")
      (libsource (lib "eagle-import") (part "R-EU_R0805"))
    )
    (comp (ref "R13")
      (value "10K")
      (footprint "eagle-import:R0805")
      (libsource (lib "eagle-import") (part "R-EU_R0805"))
    )
    (comp (ref "R14")
      (value "1K")
      (footprint "eagle-import:R0805")
      (libsource (lib "eagle-import") (part "R-EU_R0805"))
    )
    (comp (ref "R15")
      (value "10K")
      (footprint "eagle-import:R0805")
      (libsource (lib "eagle-import") (part "R-EU_R0805"))
    )
    (comp (ref "R16")
      (value "10K")
      (footprint "eagle-import:R0805")
      (libsource (lib "eagle-import") (part "R-EU_R0805"))
    )
    (comp (ref "R17")
      (value "3K3")
      (footprint "eagle-import:R0805")
      (libsource (lib "eagle-import") (part "R-EU_R0805"))
    )
    (comp (ref "SW1")
      (value "1301.9316")
      (footprint "eagle-import:TACTM-6XN")
      (libsource (lib "eagle-import") (part "TACT_SW"))
    )
    (comp (ref "X2")
      (value "SSW-105-02-S-D")
      (footprint "eagle-import:SSW-105-02-S-D")
      (libsource (lib "eagle-import") (part "SSW-105-02-S-D"))
    )
    (comp (ref "X3")
      (value "TSW-104-02-S-D_NN")
      (footprint "eagle-import:TSW-104-02-S-D-NONUM")
      (libsource (lib "eagle-import") (part "TSW-104-02-S-D_NN"))
    )
  )
  (nets
    (net (code "5") (name "+1V0") (class "Default")
      (node (ref "C46") (pin "1") (pinfunction "1_1") (pintype "passive"))
      (node (ref "C47") (pin "1") (pinfunction "1_1") (pintype "passive"))
      (node (ref "C48") (pin "1") (pinfunction "1_1") (pintype "passive"))
      (node (ref "C49") (pin "1") (pinfunction "1_1") (pintype "passive"))
      (node (ref "C50") (pin "1") (pinfunction "1_1") (pintype "passive"))
      (node (ref "C52") (pin "1") (pinfunction "1_1") (pintype "passive"))
      (node (ref "C53") (pin "1") (pinfunction "1_1") (pintype "passive"))
      (node (ref "C54") (pin "1") (pinfunction "1_1") (pintype "passive"))
      (node (ref "C55") (pin "1") (pinfunction "1_1") (pintype "passive"))
      (node (ref "C56") (pin "1") (pinfunction "1_1") (pintype "passive"))
      (node (ref "C9") (pin "1") (pinfunction "1_1") (pintype "passive"))
      (node (ref "IC18") (pin "101") (pinfunction "VDD-101_101") (pintype "power_in"))
      (node (ref "IC18") (pin "102") (pinfunction "VDD-102_102") (pintype "power_in"))
      (node (ref "IC18") (pin "11") (pinfunction "VDD-11_11") (pintype "power_in"))
      (node (ref "IC18") (pin "120") (pinfunction "VDD-120_120") (pintype "power_in"))
      (node (ref "IC18") (pin "126") (pinfunction "VDD-126_126") (pintype "power_in"))
      (node (ref "IC18") (pin "16") (pinfunction "VDD-16_16") (pintype "power_in"))
      (node (ref "IC18") (pin "17") (pinfunction "VDD-17_17") (pintype "power_in"))
      (node (ref "IC18") (pin "24") (pinfunction "VDD-24_24") (pintype "power_in"))
      (node (ref "IC18") (pin "36") (pinfunction "VDD-36_36") (pintype "power_in"))
      (node (ref "IC18") (pin "41") (pinfunction "VDD-41_41") (pintype "power_in"))
      (node (ref "IC18") (pin "49") (pinfunction "USB_VDD_49") (pintype "power_in"))
      (node (ref "IC18") (pin "56") (pinfunction "VDD-56_56") (pintype "power_in"))
      (node (ref "IC18") (pin "60") (pinfunction "VDD-60_60") (pintype "power_in"))
      (node (ref "IC18") (pin "73") (pinfunction "VDD-73_73") (pintype "power_in"))
      (node (ref "IC18") (pin "80") (pinfunction "VDD-80_80") (pintype "power_in"))
      (node (ref "IC18") (pin "81") (pinfunction "VDD-81_81") (pintype "power_in"))
      (node (ref "IC18") (pin "87") (pinfunction "VDD-87_87") (pintype "power_in"))
      (node (ref "IC8") (pin "5") (pinfunction "SENSE_5") (pintype "passive"))
      (node (ref "L3") (pin "2") (pinfunction "2_2") (pintype "passive"))
      (node (ref "R31") (pin "1") (pinfunction "1_1") (pintype "passive"))
      (node (ref "R8") (pin "2") (pinfunction "2_2") (pintype "passive"))
    )
    (net (code "6") (name "+3V3") (class "Default")
      (node (ref "C10") (pin "2") (pinfunction "2_2") (pintype "passive"))
      (node (ref "C11") (pin "2") (pinfunction "2_2") (pintype "passive"))
      (node (ref "C12") (pin "2") (pinfunction "2_2") (pintype "passive"))
      (node (ref "C13") (pin "2") (pinfunction "2_2") (pintype "passive"))
      (node (ref "C17") (pin "1") (pinfunction "1_1") (pintype "passive"))
      (node (ref "C19") (pin "1") (pinfunction "1_1") (pintype "passive"))
      (node (ref "C2") (pin "1") (pinfunction "1_1") (pintype "passive"))
      (node (ref "C21") (pin "1") (pinfunction "1_1") (pintype "passive"))
      (node (ref "C22") (pin "1") (pinfunction "1_1") (pintype "passive"))
      (node (ref "C23") (pin "1") (pinfunction "1_1") (pintype "passive"))
      (node (ref "C24") (pin "1") (pinfunction "1_1") (pintype "passive"))
      (node (ref "C25") (pin "1") (pinfunction "1_1") (pintype "passive"))
      (node (ref "C26") (pin "1") (pinfunction "1_1") (pintype "passive"))
      (node (ref "C27") (pin "1") (pinfunction "1_1") (pintype "passive"))
      (node (ref "C28") (pin "1") (pinfunction "1_1") (pintype "passive"))
      (node (ref "C29") (pin "1") (pinfunction "1_1") (pintype "passive"))
      (node (ref "C30") (pin "1") (pinfunction "1_1") (pintype "passive"))
      (node (ref "C35") (pin "1") (pinfunction "1_1") (pintype "passive"))
      (node (ref "C36") (pin "1") (pinfunction "1_1") (pintype "passive"))
      (node (ref "C37") (pin "1") (pinfunction "1_1") (pintype "passive"))
      (node (ref "C38") (pin "1") (pinfunction "1_1") (pintype "passive"))
      (node (ref "C39") (pin "1") (pinfunction "1_1") (pintype "passive"))
      (node (ref "C42") (pin "1") (pinfunction "1_1") (pintype "passive"))
      (node (ref "C43") (pin "1") (pinfunction "1_1") (pintype "passive"))
      (node (ref "C44") (pin "1") (pinfunction "1_1") (pintype "passive"))
      (node (ref "C45") (pin "1") (pinfunction "1_1") (pintype "passive"))
      (node (ref "C5") (pin "1") (pinfunction "1_1") (pintype "passive"))
      (node (ref "C51") (pin "1") (pinfunction "1_1") (pintype "passive"))
      (node (ref "C58") (pin "2") (pinfunction "2_2") (pintype "passive"))
      (node (ref "C6") (pin "2") (pinfunction "2_2") (pintype "passive"))
      (node (ref "C63") (pin "2") (pinfunction "2_2") (pintype "passive"))
      (node (ref "C74") (pin "1") (pinfunction "1_1") (pintype "passive"))
      (node (ref "C75") (pin "1") (pinfunction "1_1") (pintype "passive"))
      (node (ref "C76") (pin "1") (pinfunction "1_1") (pintype "passive"))
      (node (ref "C77") (pin "1") (pinfunction "1_1") (pintype "passive"))
      (node (ref "C80") (pin "2") (pinfunction "2_2") (pintype "passive"))
      (node (ref "C81") (pin "1") (pinfunction "1_1") (pintype "passive"))
      (node (ref "C82") (pin "1") (pinfunction "1_1") (pintype "passive"))
      (node (ref "D2") (pin "A") (pinfunction "A_A") (pintype "passive"))
      (node (ref "FB3") (pin "P$1") (pinfunction "1_P$1") (pintype "passive"))
      (node (ref "IC10") (pin "1") (pinfunction "VDD-1_1") (pintype "power_in"))
      (node (ref "IC10") (pin "14") (pinfunction "VDD-14_14") (pintype "power_in"))
      (node (ref "IC10") (pin "27") (pinfunction "VDD-27_27") (pintype "power_in"))
      (node (ref "IC10") (pin "3") (pinfunction "VDDQ-3_3") (pintype "power_in"))
      (node (ref "IC10") (pin "43") (pinfunction "VDDQ-43_43") (pintype "power_in"))
      (node (ref "IC10") (pin "49") (pinfunction "VDDQ-49_49") (pintype "power_in"))
      (node (ref "IC10") (pin "9") (pinfunction "VDDQ-9_9") (pintype "power_in"))
      (node (ref "IC11") (pin "16") (pinfunction "VCC_16") (pintype "power_in"))
      (node (ref "IC12") (pin "5") (pinfunction "VDD_5") (pintype "power_in"))
      (node (ref "IC13") (pin "8") (pinfunction "VCC_8") (pintype "power_in"))
      (node (ref "IC14") (pin "16") (pinfunction "VCC_16") (pintype "power_in"))
      (node (ref "IC18") (pin "105") (pinfunction "OTP_VCC_105") (pintype "power_in"))
      (node (ref "IC18") (pin "110") (pinfunction "VDDIOT-110_110") (pintype "power_in"))
      (node (ref "IC18") (pin "111") (pinfunction "VDDIOT-111_111") (pintype "power_in"))
      (node (ref "IC18") (pin "14") (pinfunction "VDDIOL-14_14") (pintype "power_in"))
      (node (ref "IC18") (pin "19") (pinfunction "VDDIOL-19_19") (pintype "power_in"))
      (node (ref "IC18") (pin "29") (pinfunction "VDDIOL-29_29") (pintype "power_in"))
      (node (ref "IC18") (pin "42") (pinfunction "VDDIOL-42_42") (pintype "power_in"))
      (node (ref "IC18") (pin "44") (pinfunction "USB_VDD33_44") (pintype "power_in"))
      (node (ref "IC18") (pin "52") (pinfunction "VDDIOR-52_52") (pintype "power_in"))
      (node (ref "IC18") (pin "6") (pinfunction "VDDIOL-6_6") (pintype "power_in"))
      (node (ref "IC18") (pin "67") (pinfunction "VDDIOR-67_67") (pintype "power_in"))
      (node (ref "IC18") (pin "78") (pinfunction "VDDIOR-78_78") (pintype "power_in"))
      (node (ref "IC18") (pin "83") (pinfunction "VDDIOR-83_83") (pintype "power_in"))
      (node (ref "IC18") (pin "92") (pinfunction "VDDIOR-92_92") (pintype "power_in"))
      (node (ref "IC19") (pin "6") (pinfunction "VCC_6") (pintype "passive"))
      (node (ref "IC20") (pin "6") (pinfunction "VCC_6") (pintype "passive"))
      (node (ref "IC21") (pin "5") (pinfunction "VDD_5") (pintype "power_in"))
      (node (ref "IC22") (pin "5") (pinfunction "VDD_5") (pintype "power_in"))
      (node (ref "IC23") (pin "6") (pinfunction "VDD_6") (pintype "power_in"))
      (node (ref "IC24") (pin "32") (pinfunction "IOVDD33-32_32") (pintype "power_in"))
      (node (ref "IC24") (pin "48") (pinfunction "IOVDD33-48_48") (pintype "power_in"))
      (node (ref "IC26") (pin "10") (pinfunction "~{SRCLR}_10") (pintype "input"))
      (node (ref "IC26") (pin "16") (pinfunction "VCC_16") (pintype "power_in"))
      (node (ref "IC28") (pin "9") (pinfunction "VDD_9") (pintype "power_in"))
      (node (ref "IC29") (pin "3") (pinfunction "~{WP}_3") (pintype "input"))
      (node (ref "IC29") (pin "7") (pinfunction "~{HOLD}_7") (pintype "input"))
      (node (ref "IC29") (pin "8") (pinfunction "VCC_8") (pintype "power_in"))
      (node (ref "IC3") (pin "10") (pinfunction "~{SRCLR}_10") (pintype "input"))
      (node (ref "IC3") (pin "16") (pinfunction "VCC_16") (pintype "power_in"))
      (node (ref "IC5") (pin "10") (pinfunction "~{SRCLR}_10") (pintype "input"))
      (node (ref "IC5") (pin "16") (pinfunction "VCC_16") (pintype "power_in"))
      (node (ref "IC6") (pin "5") (pinfunction "SENSE_5") (pintype "passive"))
      (node (ref "IC6") (pin "6") (pinfunction "VDD_6") (pintype "power_in"))
      (node (ref "IC7") (pin "1") (pinfunction "VDD_1") (pintype "power_in"))
      (node (ref "IC7") (pin "2") (pinfunction "M1_2") (pintype "bidirectional"))
      (node (ref "IC8") (pin "6") (pinfunction "VDD_6") (pintype "power_in"))
      (node (ref "IC9") (pin "2") (pinfunction "D_2") (pintype "input"))
      (node (ref "IC9") (pin "7") (pinfunction "~{PRE}_7") (pintype "input"))
      (node (ref "IC9") (pin "8") (pinfunction "VDD_8") (pintype "power_in"))
      (node (ref "J2") (pin "4") (pinfunction "VDD_4") (pintype "power_in"))
      (node (ref "L1") (pin "1") (pinfunction "1_1") (pintype "passive"))
      (node (ref "L2") (pin "2") (pinfunction "2_2") (pintype "passive"))
      (node (ref "LCD1") (pin "4") (pinfunction "VDD_4") (pintype "power_in"))
      (node (ref "MOD1") (pin "1") (pinfunction "3V3_1") (pintype "power_in"))
      (node (ref "PWR_3V3") (pin "A") (pinfunction "A_A") (pintype "passive"))
      (node (ref "R1") (pin "1") (pinfunction "1_1") (pintype "passive"))
      (node (ref "R10") (pin "2") (pinfunction "2_2") (pintype "passive"))
      (node (ref "R12") (pin "1") (pinfunction "1_1") (pintype "passive"))
      (node (ref "R13") (pin "1") (pinfunction "1_1") (pintype "passive"))
      (node (ref "R14") (pin "1") (pinfunction "1_1") (pintype "passive"))
      (node (ref "R16") (pin "2") (pinfunction "2_2") (pintype "passive"))
      (node (ref "R17") (pin "2") (pinfunction "2_2") (pintype "passive"))
      (node (ref "R19") (pin "2") (pinfunction "2_2") (pintype "passive"))
      (node (ref "R20") (pin "1") (pinfunction "1_1") (pintype "passive"))
      (node (ref "R26") (pin "1") (pinfunction "1_1") (pintype "passive"))
      (node (ref "R4") (pin "2") (pinfunction "2_2") (pintype "passive"))
      (node (ref "R43") (pin "1") (pinfunction "1_1") (pintype "passive"))
      (node (ref "R45") (pin "1") (pinfunction "1_1") (pintype "passive"))
      (node (ref "R46") (pin "1") (pinfunction "1_1") (pintype "passive"))
      (node (ref "R48") (pin "1") (pinfunction "1_1") (pintype "passive"))
      (node (ref "R51") (pin "1") (pinfunction "1_1") (pintype "passive"))
      (node (ref "R52") (pin "1") (pinfunction "1_1") (pintype "passive"))
      (node (ref "R65") (pin "2") (pinfunction "2_2") (pintype "passive"))
      (node (ref "R66") (pin "2") (pinfunction "2_2") (pintype "passive"))
      (node (ref "R7") (pin "2") (pinfunction "2_2") (pintype "passive"))
      (node (ref "X2") (pin "3") (pinfunction "1_3") (pintype "passive"))
      (node (ref "X3") (pin "7") (pinfunction "1_7") (pintype "passive"))
      (node (ref "X4") (pin "5") (pinfunction "1_5") (pintype "passive"))
      (node (ref "X7") (pin "12") (pinfunction "YELLOW_A_12") (pintype "passive"))
      (node (ref "X7") (pin "9") (pinfunction "GREEN-A_9") (pintype "passive"))
      (node (ref "X9") (pin "1") (pinfunction "1_1") (pintype "passive"))
      (node (ref "X9") (pin "17") (pinfunction "1_17") (pintype "passive"))
      (node (ref "X9") (pin "18") (pinfunction "1_18") (pintype "passive"))
      (node (ref "XO1") (pin "4") (pinfunction "VDD_4") (pintype "power_in"))
      (node (ref "XO2") (pin "4") (pinfunction "VDD_4") (pintype "power_in"))
    )
    (net (code "7") (name "+3V3(A)") (class "Default")
      (node (ref "C66") (pin "2") (pinfunction "2_2") (pintype "passive"))
      (node (ref "C68") (pin "2") (pinfunction "2_2") (pintype "passive"))
      (node (ref "C73") (pin "1") (pinfunction "1_1") (pintype "passive"))
      (node (ref "FB3") (pin "P$2") (pinfunction "2_P$2") (pintype "passive"))
      (node (ref "IC24") (pin "22") (pinfunction "AVDD33_22") (pintype "power_in"))
      (node (ref "X7") (pin "3") (pinfunction "CT_3") (pintype "input"))
      (node (ref "X7") (pin "6") (pinfunction "CR_6") (pintype "input"))
    )
    (net (code "8") (name "+5V") (class "Default")
      (node (ref "C41") (pin "1") (pinfunction "1_1") (pintype "passive"))
      (node (ref "IC15") (pin "5") (pinfunction "IN_5") (pintype "input"))
      (node (ref "L4") (pin "2") (pinfunction "2_2") (pintype "passive"))
      (node (ref "R23") (pin "2") (pinfunction "2_2") (pintype "passive"))
      (node (ref "X4") (pin "6") (pinfunction "1_6") (pintype "passive"))
    )
    (net (code "12") (name "1V0_EN") (class "Default")
      (node (ref "IC4") (pin "5") (pinfunction "EN_5") (pintype "input"))
      (node (ref "IC6") (pin "1") (pinfunction "~{RESET}_1") (pintype "output"))
      (node (ref "R10") (pin "1") (pinfunction "1_1") (pintype "passive"))
    )
    (net (code "13") (name "5V0") (class "Default")
      (node (ref "MOD1") (pin "6") (pinfunction "5V0_6") (pintype "power_in"))
    )
    (net (code "14") (name "AUDIO_OUT") (class "Default")
      (node (ref "IC18") (pin "62") (pinfunction "X0D12_62") (pintype "bidirectional"))
      (node (ref "IC22") (pin "2") (pinfunction "A_2") (pintype "input"))
      (node (ref "X9") (pin "10") (pinfunction "1_10") (pintype "passive"))
    )
    (net (code "15") (name "ETH_MDC") (class "Default")
      (node (ref "IC18") (pin "122") (pinfunction "X1D11_122") (pintype "bidirectional"))
      (node (ref "IC24") (pin "31") (pinfunction "MDC_31") (pintype "input"))
    )
    (net (code "16") (name "ETH_MDIO") (class "Default")
      (node (ref "IC18") (pin "121") (pinfunction "X1D10_121") (pintype "bidirectional"))
      (node (ref "IC24") (pin "30") (pinfunction "MDIO_30") (pintype "bidirectional"))
    )
    (net (code "17") (name "ETH_RST") (class "Default")
      (node (ref "IC18") (pin "18") (pinfunction "X1D37_18") (pintype "bidirectional"))
      (node (ref "IC24") (pin "29") (pinfunction "RESET_N_29") (pintype "input"))
      (node (ref "MOD1") (pin "8") (pinfunction "RST_8") (pintype "passive"))
    )
    (net (code "18") (name "ETH_RX0") (class "Default")
      (node (ref "IC18") (pin "116") (pinfunction "X1D30_116") (pintype "bidirectional"))
      (node (ref "IC24") (pin "43") (pinfunction "PHYAD1(RXD1_0)_43") (pintype "output"))
    )
    (net (code "19") (name "ETH_RX1") (class "Default")
      (node (ref "IC18") (pin "117") (pinfunction "X1D31_117") (pintype "bidirectional"))
      (node (ref "IC24") (pin "44") (pinfunction "PHYAD2(RXD1_1)_44") (pintype "output"))
    )
    (net (code "20") (name "ETH_RX2") (class "Default")
      (node (ref "IC18") (pin "118") (pinfunction "X1D32_118") (pintype "bidirectional"))
      (node (ref "IC24") (pin "45") (pinfunction "PHYAD3(RXD1_2)_45") (pintype "output"))
    )
    (net (code "21") (name "ETH_RX3") (class "Default")
      (node (ref "IC18") (pin "119") (pinfunction "X1D33_119") (pintype "bidirectional"))
      (node (ref "IC24") (pin "46") (pinfunction "PHYAD4(RXD1_3)_46") (pintype "output"))
    )
    (net (code "22") (name "ETH_RX_CLK") (class "Default")
      (node (ref "IC18") (pin "114") (pinfunction "X1D28_114") (pintype "bidirectional"))
      (node (ref "IC24") (pin "38") (pinfunction "RX_CLK_38") (pintype "output"))
    )
    (net (code "23") (name "ETH_RX_CTL") (class "Default")
      (node (ref "IC18") (pin "115") (pinfunction "X1D29_115") (pintype "bidirectional"))
      (node (ref "IC24") (pin "39") (pinfunction "MII_MODE(RX_DV)_39") (pintype "output"))
    )
    (net (code "24") (name "ETH_RX_ER") (class "Default")
      (node (ref "IC18") (pin "15") (pinfunction "X1D36_15") (pintype "bidirectional"))
      (node (ref "IC24") (pin "41") (pinfunction "MDIX_EN(RX_ER)_41") (pintype "output"))
    )
    (net (code "25") (name "ETH_TX0") (class "Default")
      (node (ref "IC18") (pin "109") (pinfunction "X1D43_109") (pintype "bidirectional"))
      (node (ref "IC24") (pin "3") (pinfunction "TXD_0_3") (pintype "input"))
    )
    (net (code "26") (name "ETH_TX1") (class "Default")
      (node (ref "IC18") (pin "108") (pinfunction "X1D42_108") (pintype "bidirectional"))
      (node (ref "IC24") (pin "4") (pinfunction "TXD_1_4") (pintype "input"))
    )
    (net (code "27") (name "ETH_TX2") (class "Default")
      (node (ref "IC18") (pin "107") (pinfunction "X1D41_107") (pintype "bidirectional"))
      (node (ref "IC24") (pin "5") (pinfunction "TXD_2_5") (pintype "input"))
    )
    (net (code "28") (name "ETH_TX3") (class "Default")
      (node (ref "IC18") (pin "106") (pinfunction "X1D40_106") (pintype "bidirectional"))
      (node (ref "IC24") (pin "6") (pinfunction "TXD_3/SNI_MODE_6") (pintype "input"))
    )
    (net (code "29") (name "ETH_TX_CLK") (class "Default")
      (node (ref "IC24") (pin "1") (pinfunction "TX_CLK_1") (pintype "output"))
      (node (ref "R42") (pin "2") (pinfunction "2_2") (pintype "passive"))
    )
    (net (code "30") (name "ETH_TX_CTL") (class "Default")
      (node (ref "IC18") (pin "113") (pinfunction "X1D27_113") (pintype "bidirectional"))
      (node (ref "IC24") (pin "2") (pinfunction "TX_EN_2") (pintype "input"))
    )
    (net (code "31") (name "GND") (class "Default")
      (node (ref "C1") (pin "2") (pinfunction "2_2") (pintype "passive"))
      (node (ref "C10") (pin "1") (pinfunction "1_1") (pintype "passive"))
      (node (ref "C11") (pin "1") (pinfunction "1_1") (pintype "passive"))
      (node (ref "C12") (pin "1") (pinfunction "1_1") (pintype "passive"))
      (node (ref "C13") (pin "1") (pinfunction "1_1") (pintype "passive"))
      (node (ref "C14") (pin "2") (pinfunction "2_2") (pintype "passive"))
      (node (ref "C15") (pin "2") (pinfunction "2_2") (pintype "passive"))
      (node (ref "C16") (pin "2") (pinfunction "2_2") (pintype "passive"))
      (node (ref "C17") (pin "2") (pinfunction "2_2") (pintype "passive"))
      (node (ref "C18") (pin "1") (pinfunction "1_1") (pintype "passive"))
      (node (ref "C19") (pin "2") (pinfunction "2_2") (pintype "passive"))
      (node (ref "C2") (pin "2") (pinfunction "2_2") (pintype "passive"))
      (node (ref "C20") (pin "2") (pinfunction "2_2") (pintype "passive"))
      (node (ref "C21") (pin "2") (pinfunction "2_2") (pintype "passive"))
      (node (ref "C22") (pin "2") (pinfunction "2_2") (pintype "passive"))
      (node (ref "C23") (pin "2") (pinfunction "2_2") (pintype "passive"))
      (node (ref "C24") (pin "2") (pinfunction "2_2") (pintype "passive"))
      (node (ref "C25") (pin "2") (pinfunction "2_2") (pintype "passive"))
      (node (ref "C26") (pin "2") (pinfunction "2_2") (pintype "passive"))
      (node (ref "C27") (pin "2") (pinfunction "2_2") (pintype "passive"))
      (node (ref "C28") (pin "2") (pinfunction "2_2") (pintype "passive"))
      (node (ref "C29") (pin "2") (pinfunction "2_2") (pintype "passive"))
      (node (ref "C30") (pin "2") (pinfunction "2_2") (pintype "passive"))
      (node (ref "C31") (pin "2") (pinfunction "2_2") (pintype "passive"))
      (node (ref "C32") (pin "2") (pinfunction "2_2") (pintype "passive"))
      (node (ref "C33") (pin "1") (pinfunction "1_1") (pintype "passive"))
      (node (ref "C35") (pin "2") (pinfunction "2_2") (pintype "passive"))
      (node (ref "C36") (pin "2") (pinfunction "2_2") (pintype "passive"))
      (node (ref "C37") (pin "2") (pinfunction "2_2") (pintype "passive"))
      (node (ref "C38") (pin "2") (pinfunction "2_2") (pintype "passive"))
      (node (ref "C39") (pin "2") (pinfunction "2_2") (pintype "passive"))
      (node (ref "C4") (pin "2") (pinfunction "2_2") (pintype "passive"))
      (node (ref "C40") (pin "2") (pinfunction "2_2") (pintype "passive"))
      (node (ref "C41") (pin "2") (pinfunction "2_2") (pintype "passive"))
      (node (ref "C42") (pin "2") (pinfunction "2_2") (pintype "passive"))
      (node (ref "C43") (pin "2") (pinfunction "2_2") (pintype "passive"))
      (node (ref "C44") (pin "2") (pinfunction "2_2") (pintype "passive"))
      (node (ref "C45") (pin "2") (pinfunction "2_2") (pintype "passive"))
      (node (ref "C46") (pin "2") (pinfunction "2_2") (pintype "passive"))
      (node (ref "C47") (pin "2") (pinfunction "2_2") (pintype "passive"))
      (node (ref "C48") (pin "2") (pinfunction "2_2") (pintype "passive"))
      (node (ref "C49") (pin "2") (pinfunction "2_2") (pintype "passive"))
      (node (ref "C5") (pin "2") (pinfunction "2_2") (pintype "passive"))
      (node (ref "C50") (pin "2") (pinfunction "2_2") (pintype "passive"))
      (node (ref "C51") (pin "2") (pinfunction "2_2") (pintype "passive"))
      (node (ref "C52") (pin "2") (pinfunction "2_2") (pintype "passive"))
      (node (ref "C53") (pin "2") (pinfunction "2_2") (pintype "passive"))
      (node (ref "C54") (pin "2") (pinfunction "2_2") (pintype "passive"))
      (node (ref "C55") (pin "2") (pinfunction "2_2") (pintype "passive"))
      (node (ref "C56") (pin "2") (pinfunction "2_2") (pintype "passive"))
      (node (ref "C57") (pin "2") (pinfunction "2_2") (pintype "passive"))
      (node (ref "C58") (pin "1") (pinfunction "1_1") (pintype "passive"))
      (node (ref "C59") (pin "2") (pinfunction "2_2") (pintype "passive"))
      (node (ref "C6") (pin "1") (pinfunction "1_1") (pintype "passive"))
      (node (ref "C60") (pin "2") (pinfunction "2_2") (pintype "passive"))
      (node (ref "C61") (pin "2") (pinfunction "2_2") (pintype "passive"))
      (node (ref "C63") (pin "1") (pinfunction "1_1") (pintype "passive"))
      (node (ref "C64") (pin "1") (pinfunction "1_1") (pintype "passive"))
      (node (ref "C65") (pin "2") (pinfunction "2_2") (pintype "passive"))
      (node (ref "C66") (pin "1") (pinfunction "1_1") (pintype "passive"))
      (node (ref "C67") (pin "2") (pinfunction "2_2") (pintype "passive"))
      (node (ref "C68") (pin "1") (pinfunction "1_1") (pintype "passive"))
      (node (ref "C69") (pin "2") (pinfunction "2_2") (pintype "passive"))
      (node (ref "C70") (pin "2") (pinfunction "2_2") (pintype "passive"))
      (node (ref "C71") (pin "-") (pinfunction "-_-") (pintype "passive"))
      (node (ref "C72") (pin "2") (pinfunction "2_2") (pintype "passive"))
      (node (ref "C73") (pin "2") (pinfunction "2_2") (pintype "passive"))
      (node (ref "C74") (pin "2") (pinfunction "2_2") (pintype "passive"))
      (node (ref "C75") (pin "2") (pinfunction "2_2") (pintype "passive"))
      (node (ref "C76") (pin "2") (pinfunction "2_2") (pintype "passive"))
      (node (ref "C77") (pin "2") (pinfunction "2_2") (pintype "passive"))
      (node (ref "C78") (pin "1") (pinfunction "1_1") (pintype "passive"))
      (node (ref "C79") (pin "2") (pinfunction "-_2") (pintype "passive"))
      (node (ref "C8") (pin "2") (pinfunction "2_2") (pintype "passive"))
      (node (ref "C80") (pin "1") (pinfunction "1_1") (pintype "passive"))
      (node (ref "C81") (pin "2") (pinfunction "2_2") (pintype "passive"))
      (node (ref "C82") (pin "2") (pinfunction "2_2") (pintype "passive"))
      (node (ref "C9") (pin "2") (pinfunction "2_2") (pintype "passive"))
      (node (ref "FB2") (pin "P$1") (pinfunction "1_P$1") (pintype "passive"))
      (node (ref "IC1") (pin "2") (pinfunction "GND_2") (pintype "power_in"))
      (node (ref "IC10") (pin "12") (pinfunction "GNDQ-12_12") (pintype "power_in"))
      (node (ref "IC10") (pin "28") (pinfunction "GND-28_28") (pintype "power_in"))
      (node (ref "IC10") (pin "41") (pinfunction "GND_41") (pintype "power_in"))
      (node (ref "IC10") (pin "46") (pinfunction "GNDQ-46_46") (pintype "power_in"))
      (node (ref "IC10") (pin "52") (pinfunction "GNDQ-52_52") (pintype "power_in"))
      (node (ref "IC10") (pin "54") (pinfunction "GND-54_54") (pintype "power_in"))
      (node (ref "IC10") (pin "6") (pinfunction "GNDQ-6_6") (pintype "power_in"))
      (node (ref "IC11") (pin "12") (pinfunction "4A_12") (pintype "passive"))
      (node (ref "IC11") (pin "15") (pinfunction "~{OE}_15") (pintype "bidirectional"))
      (node (ref "IC11") (pin "8") (pinfunction "GND_8") (pintype "power_in"))
      (node (ref "IC12") (pin "3") (pinfunction "VSS_3") (pintype "power_in"))
      (node (ref "IC13") (pin "4") (pinfunction "GND_4") (pintype "power_in"))
      (node (ref "IC14") (pin "15") (pinfunction "~{OE}_15") (pintype "bidirectional"))
      (node (ref "IC14") (pin "8") (pinfunction "GND_8") (pintype "power_in"))
      (node (ref "IC15") (pin "2") (pinfunction "GND_2") (pintype "power_in"))
      (node (ref "IC16") (pin "1") (pinfunction "GND_1") (pintype "passive"))
      (node (ref "IC17") (pin "1") (pinfunction "GND_1") (pintype "power_in"))
      (node (ref "IC18") (pin "104") (pinfunction "PLL_AGND_104") (pintype "power_in"))
      (node (ref "IC18") (pin "PAD") (pinfunction "VSS_PAD") (pintype "power_in"))
      (node (ref "IC19") (pin "3") (pinfunction "GND_3") (pintype "power_in"))
      (node (ref "IC2") (pin "1") (pinfunction "GND_1") (pintype "power_in"))
      (node (ref "IC20") (pin "3") (pinfunction "GND_3") (pintype "power_in"))
      (node (ref "IC21") (pin "3") (pinfunction "VSS_3") (pintype "power_in"))
      (node (ref "IC22") (pin "3") (pinfunction "VSS_3") (pintype "power_in"))
      (node (ref "IC23") (pin "7") (pinfunction "GND_7") (pintype "passive"))
      (node (ref "IC23") (pin "TP") (pinfunction "TP_TP") (pintype "passive"))
      (node (ref "IC24") (pin "15") (pinfunction "AGND-15_15") (pintype "power_in"))
      (node (ref "IC24") (pin "19") (pinfunction "AGND-19_19") (pintype "power_in"))
      (node (ref "IC24") (pin "35") (pinfunction "IOGND-35_35") (pintype "power_in"))
      (node (ref "IC24") (pin "36") (pinfunction "DGND_36") (pintype "power_in"))
      (node (ref "IC24") (pin "47") (pinfunction "IOGND-47_47") (pintype "power_in"))
      (node (ref "IC24") (pin "PAD") (pinfunction "GND_PAD") (pintype "power_in"))
      (node (ref "IC26") (pin "13") (pinfunction "~{OE}_13") (pintype "input"))
      (node (ref "IC26") (pin "8") (pinfunction "GND_8") (pintype "power_in"))
      (node (ref "IC27") (pin "7") (pinfunction "VSS_7") (pintype "passive"))
      (node (ref "IC28") (pin "10") (pinfunction "VSS_10") (pintype "power_in"))
      (node (ref "IC28") (pin "15") (pinfunction "A0_15") (pintype "input"))
      (node (ref "IC28") (pin "16") (pinfunction "A1_16") (pintype "input"))
      (node (ref "IC28") (pin "17") (pinfunction "A2_17") (pintype "input"))
      (node (ref "IC29") (pin "4") (pinfunction "GND_4") (pintype "passive"))
      (node (ref "IC3") (pin "13") (pinfunction "~{OE}_13") (pintype "input"))
      (node (ref "IC3") (pin "8") (pinfunction "GND_8") (pintype "power_in"))
      (node (ref "IC4") (pin "1") (pinfunction "GND_1") (pintype "power_in"))
      (node (ref "IC5") (pin "13") (pinfunction "~{OE}_13") (pintype "input"))
      (node (ref "IC5") (pin "8") (pinfunction "GND_8") (pintype "power_in"))
      (node (ref "IC6") (pin "2") (pinfunction "GND_2") (pintype "power_in"))
      (node (ref "IC7") (pin "14") (pinfunction "SX+_14") (pintype "bidirectional"))
      (node (ref "IC7") (pin "17") (pinfunction "5WSX-_17") (pintype "input"))
      (node (ref "IC7") (pin "20") (pinfunction "VSS_20") (pintype "power_in"))
      (node (ref "IC7") (pin "3") (pinfunction "SY-_3") (pintype "bidirectional"))
      (node (ref "IC7") (pin "4") (pinfunction "M2_4") (pintype "input"))
      (node (ref "IC7") (pin "7") (pinfunction "SY+_7") (pintype "bidirectional"))
      (node (ref "IC8") (pin "2") (pinfunction "GND_2") (pintype "power_in"))
      (node (ref "IC9") (pin "4") (pinfunction "VSS_4") (pintype "power_in"))
      (node (ref "J1") (pin "5") (pinfunction "GND_5") (pintype "passive"))
      (node (ref "J2") (pin "6") (pinfunction "VSS_6") (pintype "power_in"))
      (node (ref "J2") (pin "S") (pinfunction "SH_S") (pintype "passive"))
      (node (ref "J2") (pin "SW2") (pinfunction "SW2_SW2") (pintype "passive"))
      (node (ref "JP1") (pin "3") (pinfunction "3_3") (pintype "passive"))
      (node (ref "LCD1") (pin "13") (pinfunction "G0_13") (pintype "input"))
      (node (ref "LCD1") (pin "14") (pinfunction "G1_14") (pintype "input"))
      (node (ref "LCD1") (pin "21") (pinfunction "B0_21") (pintype "input"))
      (node (ref "LCD1") (pin "22") (pinfunction "B1_22") (pintype "input"))
      (node (ref "LCD1") (pin "23") (pinfunction "B2_23") (pintype "input"))
      (node (ref "LCD1") (pin "29") (pinfunction "GND-29_29") (pintype "power_in"))
      (node (ref "LCD1") (pin "3") (pinfunction "GND-3_3") (pintype "power_in"))
      (node (ref "LCD1") (pin "5") (pinfunction "R0_5") (pintype "input"))
      (node (ref "LCD1") (pin "6") (pinfunction "R1_6") (pintype "input"))
      (node (ref "LCD1") (pin "7") (pinfunction "R2_7") (pintype "input"))
      (node (ref "MOD1") (pin "7") (pinfunction "GND_7") (pintype "power_in"))
      (node (ref "OK1") (pin "2") (pinfunction "C_2") (pintype "passive"))
      (node (ref "OK1") (pin "4") (pinfunction "C_4") (pintype "passive"))
      (node (ref "OK2") (pin "5") (pinfunction "EMIT_5") (pintype "passive"))
      (node (ref "OK2") (pin "7") (pinfunction "EMIT_7") (pintype "passive"))
      (node (ref "R15") (pin "2") (pinfunction "2_2") (pintype "passive"))
      (node (ref "R2") (pin "1") (pinfunction "1_1") (pintype "passive"))
      (node (ref "R21") (pin "2") (pinfunction "2_2") (pintype "passive"))
      (node (ref "R22") (pin "2") (pinfunction "2_2") (pintype "passive"))
      (node (ref "R24") (pin "1") (pinfunction "1_1") (pintype "passive"))
      (node (ref "R3") (pin "2") (pinfunction "2_2") (pintype "passive"))
      (node (ref "R37") (pin "2") (pinfunction "2_2") (pintype "passive"))
      (node (ref "R5") (pin "1") (pinfunction "1_1") (pintype "passive"))
      (node (ref "R53") (pin "1") (pinfunction "1_1") (pintype "passive"))
      (node (ref "R55") (pin "1") (pinfunction "1_1") (pintype "passive"))
      (node (ref "R56") (pin "1") (pinfunction "1_1") (pintype "passive"))
      (node (ref "R57") (pin "1") (pinfunction "1_1") (pintype "passive"))
      (node (ref "R6") (pin "1") (pinfunction "1_1") (pintype "passive"))
      (node (ref "R9") (pin "1") (pinfunction "1_1") (pintype "passive"))
      (node (ref "SW1") (pin "1") (pinfunction "1_1") (pintype "passive"))
      (node (ref "SW1") (pin "2") (pinfunction "2_2") (pintype "passive"))
      (node (ref "SW1") (pin "5") (pinfunction "5-GND_5") (pintype "passive"))
      (node (ref "X1") (pin "1") (pinfunction "1_1") (pintype "power_in"))
      (node (ref "X1") (pin "3") (pinfunction "3_3") (pintype "power_in"))
      (node (ref "X3") (pin "8") (pinfunction "1_8") (pintype "passive"))
      (node (ref "X4") (pin "2") (pinfunction "1_2") (pintype "passive"))
      (node (ref "X4") (pin "4") (pinfunction "1_4") (pintype "passive"))
      (node (ref "X5") (pin "12") (pinfunction "12_12") (pintype "passive"))
      (node (ref "X5") (pin "16") (pinfunction "16_16") (pintype "passive"))
      (node (ref "X5") (pin "20") (pinfunction "20_20") (pintype "passive"))
      (node (ref "X5") (pin "4") (pinfunction "4_4") (pintype "passive"))
      (node (ref "X5") (pin "8") (pinfunction "8_8") (pintype "passive"))
      (node (ref "X7") (pin "4") (pinfunction "SH_4") (pintype "input"))
      (node (ref "X7") (pin "5") (pinfunction "SH_5") (pintype "input"))
      (node (ref "X7") (pin "SH1") (pinfunction "SH_SH1") (pintype "input"))
      (node (ref "X7") (pin "SH2") (pinfunction "SH_SH2") (pintype "input"))
      (node (ref "X8") (pin "2") (pinfunction "1_2") (pintype "passive"))
      (node (ref "X8") (pin "4") (pinfunction "1_4") (pintype "passive"))
      (node (ref "X8") (pin "6") (pinfunction "1_6") (pintype "passive"))
      (node (ref "X9") (pin "19") (pinfunction "1_19") (pintype "passive"))
      (node (ref "X9") (pin "2") (pinfunction "1_2") (pintype "passive"))
      (node (ref "X9") (pin "20") (pinfunction "1_20") (pintype "passive"))
      (node (ref "X9") (pin "9") (pinfunction "1_9") (pintype "passive"))
      (node (ref "XO1") (pin "2") (pinfunction "GND_2") (pintype "power_in"))
      (node (ref "XO2") (pin "2") (pinfunction "GND_2") (pintype "power_in"))
      (node (ref "ZD3") (pin "A") (pinfunction "A_A") (pintype "passive"))
      (node (ref "ZD4") (pin "A") (pinfunction "A_A") (pintype "passive"))
      (node (ref "ZD5") (pin "A") (pinfunction "A_A") (pintype "passive"))
      (node (ref "ZD6") (pin "A") (pinfunction "A_A") (pintype "passive"))
    )
    (net (code "32") (name "GPIO38") (class "Default")
      (node (ref "IC18") (pin "5") (pinfunction "X0D38_5") (pintype "bidirectional"))
      (node (ref "X4") (pin "3") (pinfunction "1_3") (pintype "passive"))
    )
    (net (code "33") (name "GPIO39") (class "Default")
      (node (ref "IC18") (pin "7") (pinfunction "X0D39_7") (pintype "bidirectional"))
      (node (ref "X4") (pin "1") (pinfunction "1_1") (pintype "passive"))
    )
    (net (code "34") (name "IOEXP_DINP1") (class "Default")
      (node (ref "IC28") (pin "24") (pinfunction "GPA3_24") (pintype "bidirectional"))
      (node (ref "R58") (pin "2") (pinfunction "2_2") (pintype "passive"))
      (node (ref "ZD4") (pin "C") (pinfunction "C_C") (pintype "passive"))
    )
    (net (code "35") (name "IOEXP_DINP2") (class "Default")
      (node (ref "IC28") (pin "25") (pinfunction "GPA4_25") (pintype "bidirectional"))
      (node (ref "R59") (pin "2") (pinfunction "2_2") (pintype "passive"))
      (node (ref "ZD5") (pin "C") (pinfunction "C_C") (pintype "passive"))
    )
    (net (code "36") (name "IOEXP_DINP3") (class "Default")
      (node (ref "IC28") (pin "26") (pinfunction "GPA5_26") (pintype "bidirectional"))
      (node (ref "R60") (pin "2") (pinfunction "2_2") (pintype "passive"))
      (node (ref "ZD6") (pin "C") (pinfunction "C_C") (pintype "passive"))
    )
    (net (code "37") (name "IOEXP_LED1") (class "Default")
      (node (ref "IC28") (pin "21") (pinfunction "GPA0_21") (pintype "bidirectional"))
      (node (ref "LED1") (pin "A") (pinfunction "A_A") (pintype "passive"))
    )
    (net (code "38") (name "IOEXP_LED2") (class "Default")
      (node (ref "IC28") (pin "22") (pinfunction "GPA1_22") (pintype "bidirectional"))
      (node (ref "LED2") (pin "A") (pinfunction "A_A") (pintype "passive"))
    )
    (net (code "39") (name "IOEXP_OCI1") (class "Default")
      (node (ref "IC28") (pin "1") (pinfunction "GPB0_1") (pintype "bidirectional"))
      (node (ref "OK2") (pin "8") (pinfunction "COL_8") (pintype "passive"))
      (node (ref "R66") (pin "1") (pinfunction "1_1") (pintype "passive"))
    )
    (net (code "40") (name "IOEXP_OCI2") (class "Default")
      (node (ref "IC28") (pin "2") (pinfunction "GPB1_2") (pintype "bidirectional"))
      (node (ref "OK2") (pin "6") (pinfunction "COL_6") (pintype "passive"))
      (node (ref "R65") (pin "1") (pinfunction "1_1") (pintype "passive"))
    )
    (net (code "41") (name "IOEXP_OCO1") (class "Default")
      (node (ref "IC28") (pin "27") (pinfunction "GPA6_27") (pintype "bidirectional"))
      (node (ref "R61") (pin "2") (pinfunction "2_2") (pintype "passive"))
    )
    (net (code "42") (name "IOEXP_OCO2") (class "Default")
      (node (ref "IC28") (pin "28") (pinfunction "GPA7_28") (pintype "bidirectional"))
      (node (ref "R62") (pin "2") (pinfunction "2_2") (pintype "passive"))
    )
    (net (code "43") (name "IPEXP_LED3") (class "Default")
      (node (ref "IC28") (pin "23") (pinfunction "GPA2_23") (pintype "bidirectional"))
      (node (ref "LED3") (pin "A") (pinfunction "A_A") (pintype "passive"))
    )
    (net (code "44") (name "LATCH_IN") (class "Default")
      (node (ref "IC11") (pin "9") (pinfunction "3A_9") (pintype "passive"))
      (node (ref "X3") (pin "2") (pinfunction "1_2") (pintype "passive"))
    )
    (net (code "45") (name "LATCH_OUT") (class "Default")
      (node (ref "IC11") (pin "11") (pinfunction "3B1_11") (pintype "passive"))
      (node (ref "IC9") (pin "1") (pinfunction "CLK_1") (pintype "input"))
      (node (ref "R13") (pin "2") (pinfunction "2_2") (pintype "passive"))
    )
    (net (code "46") (name "LCD_0") (class "Default")
      (node (ref "IC3") (pin "15") (pinfunction "Q0/A_15") (pintype "output"))
      (node (ref "LCD1") (pin "8") (pinfunction "R3_8") (pintype "input"))
    )
    (net (code "47") (name "LCD_1") (class "Default")
      (node (ref "IC3") (pin "1") (pinfunction "Q1/B_1") (pintype "output"))
      (node (ref "LCD1") (pin "9") (pinfunction "R4_9") (pintype "input"))
    )
    (net (code "48") (name "LCD_2") (class "Default")
      (node (ref "IC3") (pin "2") (pinfunction "Q2/C_2") (pintype "output"))
      (node (ref "LCD1") (pin "10") (pinfunction "R5_10") (pintype "input"))
    )
    (net (code "49") (name "LCD_3") (class "Default")
      (node (ref "IC3") (pin "3") (pinfunction "Q3/D_3") (pintype "output"))
      (node (ref "LCD1") (pin "11") (pinfunction "R6_11") (pintype "input"))
    )
    (net (code "50") (name "LCD_4") (class "Default")
      (node (ref "IC3") (pin "4") (pinfunction "Q4/E_4") (pintype "output"))
      (node (ref "LCD1") (pin "12") (pinfunction "R7_12") (pintype "input"))
    )
    (net (code "51") (name "LCD_5") (class "Default")
      (node (ref "IC3") (pin "5") (pinfunction "Q5/F_5") (pintype "output"))
      (node (ref "LCD1") (pin "15") (pinfunction "G2_15") (pintype "input"))
    )
    (net (code "52") (name "LCD_6") (class "Default")
      (node (ref "IC3") (pin "6") (pinfunction "Q6/G_6") (pintype "output"))
      (node (ref "LCD1") (pin "16") (pinfunction "G3_16") (pintype "input"))
    )
    (net (code "53") (name "LCD_7") (class "Default")
      (node (ref "IC3") (pin "7") (pinfunction "Q7/H_7") (pintype "output"))
      (node (ref "LCD1") (pin "17") (pinfunction "G4_17") (pintype "input"))
    )
    (net (code "54") (name "LCD_8") (class "Default")
      (node (ref "IC5") (pin "15") (pinfunction "Q0/A_15") (pintype "output"))
      (node (ref "LCD1") (pin "18") (pinfunction "G5_18") (pintype "input"))
    )
    (net (code "55") (name "LCD_9") (class "Default")
      (node (ref "IC5") (pin "1") (pinfunction "Q1/B_1") (pintype "output"))
      (node (ref "LCD1") (pin "19") (pinfunction "G6_19") (pintype "input"))
    )
    (net (code "56") (name "LCD_10") (class "Default")
      (node (ref "IC5") (pin "2") (pinfunction "Q2/C_2") (pintype "output"))
      (node (ref "LCD1") (pin "20") (pinfunction "G7_20") (pintype "input"))
    )
    (net (code "57") (name "LCD_11") (class "Default")
      (node (ref "IC5") (pin "3") (pinfunction "Q3/D_3") (pintype "output"))
      (node (ref "LCD1") (pin "24") (pinfunction "B3_24") (pintype "input"))
    )
    (net (code "58") (name "LCD_12") (class "Default")
      (node (ref "IC5") (pin "4") (pinfunction "Q4/E_4") (pintype "output"))
      (node (ref "LCD1") (pin "25") (pinfunction "B4_25") (pintype "input"))
    )
    (net (code "59") (name "LCD_13") (class "Default")
      (node (ref "IC5") (pin "5") (pinfunction "Q5/F_5") (pintype "output"))
      (node (ref "LCD1") (pin "26") (pinfunction "B5_26") (pintype "input"))
    )
    (net (code "60") (name "LCD_14") (class "Default")
      (node (ref "IC5") (pin "6") (pinfunction "Q6/G_6") (pintype "output"))
      (node (ref "LCD1") (pin "27") (pinfunction "B6_27") (pintype "input"))
    )
    (net (code "61") (name "LCD_15") (class "Default")
      (node (ref "IC5") (pin "7") (pinfunction "Q7/H_7") (pintype "output"))
      (node (ref "LCD1") (pin "28") (pinfunction "B7_28") (pintype "input"))
    )
    (net (code "62") (name "LCD_CLK") (class "Default")
      (node (ref "IC18") (pin "88") (pinfunction "X0D24_88") (pintype "bidirectional"))
      (node (ref "LCD1") (pin "30") (pinfunction "CLK_30") (pintype "input"))
    )
    (net (code "63") (name "LCD_DE") (class "Default")
      (node (ref "IC18") (pin "66") (pinfunction "X0D23_66") (pintype "bidirectional"))
      (node (ref "LCD1") (pin "34") (pinfunction "DE/NC2_34") (pintype "passive"))
    )
    (net (code "64") (name "LCD_HSYNC") (class "Default")
      (node (ref "IC18") (pin "89") (pinfunction "X0D25_89") (pintype "bidirectional"))
      (node (ref "LCD1") (pin "32") (pinfunction "HSYNC_32") (pintype "input"))
    )
    (net (code "65") (name "LCD_VSYNC") (class "Default")
      (node (ref "IC18") (pin "64") (pinfunction "X0D22_64") (pintype "bidirectional"))
      (node (ref "LCD1") (pin "33") (pinfunction "VSYNC_33") (pintype "input"))
    )
    (net (code "66") (name "LED_ACT") (class "Default")
      (node (ref "IC24") (pin "26") (pinfunction "AN_EN(LED_ACT/COL)_26") (pintype "output"))
      (node (ref "R43") (pin "2") (pinfunction "2_2") (pintype "passive"))
      (node (ref "R49") (pin "2") (pinfunction "2_2") (pintype "passive"))
    )
    (net (code "67") (name "LED_LINK") (class "Default")
      (node (ref "IC24") (pin "28") (pinfunction "AN_0(LED_LINK)_28") (pintype "output"))
      (node (ref "R48") (pin "2") (pinfunction "2_2") (pintype "passive"))
      (node (ref "R50") (pin "2") (pinfunction "2_2") (pintype "passive"))
    )
    (net (code "68") (name "LED_SPEED") (class "Default")
      (node (ref "IC24") (pin "27") (pinfunction "AN_1(LED_SPEED)_27") (pintype "output"))
      (node (ref "R46") (pin "2") (pinfunction "2_2") (pintype "passive"))
      (node (ref "SPEED") (pin "C") (pinfunction "C_C") (pintype "passive"))
    )
    (net (code "69") (name "Net-(C59-Pad1)") (class "Default")
      (node (ref "C59") (pin "1") (pinfunction "1_1") (pintype "passive"))
      (node (ref "R35") (pin "2") (pinfunction "2_2") (pintype "passive"))
    )
    (net (code "70") (name "Net-(C61-Pad1)") (class "Default")
      (node (ref "C61") (pin "1") (pinfunction "1_1") (pintype "passive"))
      (node (ref "R33") (pin "1") (pinfunction "1_1") (pintype "passive"))
      (node (ref "R34") (pin "2") (pinfunction "2_2") (pintype "passive"))
    )
    (net (code "71") (name "Net-(C62-Pad1)") (class "Default")
      (node (ref "C62") (pin "1") (pinfunction "1_1") (pintype "passive"))
      (node (ref "R36") (pin "2") (pinfunction "2_2") (pintype "passive"))
    )
    (net (code "72") (name "Net-(C62-Pad2)") (class "Default")
      (node (ref "C62") (pin "2") (pinfunction "2_2") (pintype "passive"))
      (node (ref "R34") (pin "1") (pinfunction "1_1") (pintype "passive"))
    )
    (net (code "73") (name "Net-(C65-Pad1)") (class "Default")
      (node (ref "C65") (pin "1") (pinfunction "1_1") (pintype "passive"))
      (node (ref "R40") (pin "1") (pinfunction "1_1") (pintype "passive"))
      (node (ref "R41") (pin "2") (pinfunction "2_2") (pintype "passive"))
    )
    (net (code "74") (name "Net-(C67-Pad1)") (class "Default")
      (node (ref "C67") (pin "1") (pinfunction "1_1") (pintype "passive"))
      (node (ref "R44") (pin "1") (pinfunction "1_1") (pintype "passive"))
      (node (ref "R47") (pin "2") (pinfunction "2_2") (pintype "passive"))
    )
    (net (code "75") (name "Net-(C79-+)") (class "Default")
      (node (ref "C79") (pin "1") (pinfunction "+_1") (pintype "passive"))
      (node (ref "R54") (pin "1") (pinfunction "1_1") (pintype "passive"))
    )
    (net (code "76") (name "Net-(D3-PadA)") (class "Default")
      (node (ref "D3") (pin "A") (pinfunction "A_A") (pintype "passive"))
      (node (ref "R63") (pin "2") (pinfunction "2_2") (pintype "passive"))
    )
    (net (code "77") (name "Net-(D4-PadA)") (class "Default")
      (node (ref "D4") (pin "A") (pinfunction "A_A") (pintype "passive"))
      (node (ref "R64") (pin "2") (pinfunction "2_2") (pintype "passive"))
    )
    (net (code "78") (name "Net-(F1-P$1)") (class "Default")
      (node (ref "F1") (pin "1") (pinfunction "P$1_1") (pintype "bidirectional"))
      (node (ref "X1") (pin "2") (pinfunction "2_2") (pintype "power_in"))
    )
    (net (code "79") (name "Net-(F1-P$2)") (class "Default")
      (node (ref "F1") (pin "2") (pinfunction "P$2_2") (pintype "bidirectional"))
      (node (ref "Q1") (pin "3") (pinfunction "D_3") (pintype "passive"))
      (node (ref "ZD3") (pin "C") (pinfunction "C_C") (pintype "passive"))
    )
    (net (code "80") (name "Net-(FB1-2)") (class "Default")
      (node (ref "FB1") (pin "P$2") (pinfunction "2_P$2") (pintype "passive"))
      (node (ref "J1") (pin "1") (pinfunction "VCC_1") (pintype "passive"))
    )
    (net (code "81") (name "Net-(FB2-2)") (class "Default")
      (node (ref "FB2") (pin "P$2") (pinfunction "2_P$2") (pintype "passive"))
      (node (ref "J1") (pin "SH1") (pinfunction "SH1_SH1") (pintype "bidirectional"))
      (node (ref "J1") (pin "SH1.1") (pinfunction "SH1_SH1.1") (pintype "bidirectional"))
      (node (ref "J1") (pin "SH2") (pinfunction "SH2_SH2") (pintype "bidirectional"))
      (node (ref "J1") (pin "SH2.2") (pinfunction "SH2_SH2.2") (pintype "bidirectional"))
    )
    (net (code "82") (name "Net-(IC1-SW)") (class "Default")
      (node (ref "D1") (pin "A") (pinfunction "A_A") (pintype "passive"))
      (node (ref "IC1") (pin "1") (pinfunction "SW_1") (pintype "power_in"))
      (node (ref "L1") (pin "2") (pinfunction "2_2") (pintype "passive"))
    )
    (net (code "83") (name "Net-(IC1-VIN)") (class "Default")
      (node (ref "IC1") (pin "5") (pinfunction "VIN_5") (pintype "power_in"))
      (node (ref "R1") (pin "2") (pinfunction "2_2") (pintype "passive"))
    )
    (net (code "84") (name "Net-(IC2-SW)") (class "Default")
      (node (ref "C3") (pin "1") (pinfunction "1_1") (pintype "passive"))
      (node (ref "IC2") (pin "2") (pinfunction "SW_2") (pintype "output"))
      (node (ref "L2") (pin "1") (pinfunction "1_1") (pintype "passive"))
    )
    (net (code "85") (name "Net-(IC2-VBST)") (class "Default")
      (node (ref "C3") (pin "2") (pinfunction "2_2") (pintype "passive"))
      (node (ref "IC2") (pin "6") (pinfunction "VBST_6") (pintype "passive"))
    )
    (net (code "86") (name "Net-(IC2-VFB)") (class "Default")
      (node (ref "IC2") (pin "4") (pinfunction "VFB_4") (pintype "passive"))
      (node (ref "R4") (pin "1") (pinfunction "1_1") (pintype "passive"))
      (node (ref "R6") (pin "2") (pinfunction "2_2") (pintype "passive"))
    )
    (net (code "87") (name "Net-(IC3-~{Q7{slash}H})") (class "Default")
      (node (ref "IC3") (pin "9") (pinfunction "~{Q7/H}_9") (pintype "output"))
      (node (ref "IC5") (pin "14") (pinfunction "SER_14") (pintype "input"))
    )
    (net (code "88") (name "Net-(IC4-SW)") (class "Default")
      (node (ref "C7") (pin "1") (pinfunction "1_1") (pintype "passive"))
      (node (ref "IC4") (pin "2") (pinfunction "SW_2") (pintype "output"))
      (node (ref "L3") (pin "1") (pinfunction "1_1") (pintype "passive"))
    )
    (net (code "89") (name "Net-(IC4-VBST)") (class "Default")
      (node (ref "C7") (pin "2") (pinfunction "2_2") (pintype "passive"))
      (node (ref "IC4") (pin "6") (pinfunction "VBST_6") (pintype "passive"))
    )
    (net (code "90") (name "Net-(IC4-VFB)") (class "Default")
      (node (ref "IC4") (pin "4") (pinfunction "VFB_4") (pintype "passive"))
      (node (ref "R8") (pin "1") (pinfunction "1_1") (pintype "passive"))
      (node (ref "R9") (pin "2") (pinfunction "2_2") (pintype "passive"))
    )
    (net (code "91") (name "Net-(IC6-CT)") (class "Default")
      (node (ref "C14") (pin "1") (pinfunction "1_1") (pintype "passive"))
      (node (ref "IC6") (pin "4") (pinfunction "CT_4") (pintype "passive"))
    )
    (net (code "92") (name "Net-(IC7-WAKE)") (class "Default")
      (node (ref "IC7") (pin "5") (pinfunction "WAKE_5") (pintype "input"))
      (node (ref "R11") (pin "1") (pinfunction "1_1") (pintype "passive"))
    )
    (net (code "93") (name "Net-(IC7-X+)") (class "Default")
      (node (ref "IC7") (pin "18") (pinfunction "X+_18") (pintype "bidirectional"))
      (node (ref "LCD1") (pin "37") (pinfunction "XR_37") (pintype "passive"))
    )
    (net (code "94") (name "Net-(IC7-X-)") (class "Default")
      (node (ref "C16") (pin "1") (pinfunction "1_1") (pintype "passive"))
      (node (ref "IC7") (pin "19") (pinfunction "X-_19") (pintype "bidirectional"))
      (node (ref "LCD1") (pin "39") (pinfunction "XL_39") (pintype "passive"))
      (node (ref "R11") (pin "2") (pinfunction "2_2") (pintype "passive"))
    )
    (net (code "95") (name "Net-(IC7-Y+)") (class "Default")
      (node (ref "IC7") (pin "15") (pinfunction "Y+_15") (pintype "bidirectional"))
      (node (ref "LCD1") (pin "40") (pinfunction "YU_40") (pintype "passive"))
    )
    (net (code "96") (name "Net-(IC7-Y-)") (class "Default")
      (node (ref "C15") (pin "1") (pinfunction "1_1") (pintype "passive"))
      (node (ref "IC7") (pin "16") (pinfunction "Y-_16") (pintype "bidirectional"))
      (node (ref "LCD1") (pin "38") (pinfunction "YD_38") (pintype "passive"))
    )
    (net (code "97") (name "Net-(IC8-CT)") (class "Default")
      (node (ref "C20") (pin "1") (pinfunction "1_1") (pintype "passive"))
      (node (ref "IC8") (pin "4") (pinfunction "CT_4") (pintype "passive"))
    )
    (net (code "98") (name "Net-(IC8-~{MR})") (class "Default")
      (node (ref "C18") (pin "2") (pinfunction "2_2") (pintype "passive"))
      (node (ref "IC8") (pin "3") (pinfunction "~{MR}_3") (pintype "passive"))
      (node (ref "SW1") (pin "3") (pinfunction "3_3") (pintype "passive"))
      (node (ref "SW1") (pin "4") (pinfunction "4_4") (pintype "passive"))
    )
    (net (code "99") (name "Net-(IC9A-Q)") (class "Default")
      (node (ref "IC9") (pin "5") (pinfunction "Q_5") (pintype "output"))
      (node (ref "X2") (pin "1") (pinfunction "1_1") (pintype "passive"))
    )
    (net (code "100") (name "Net-(IC10-CKE)") (class "Default")
      (node (ref "IC10") (pin "37") (pinfunction "CKE_37") (pintype "input"))
      (node (ref "R16") (pin "1") (pinfunction "1_1") (pintype "passive"))
    )
    (net (code "101") (name "Net-(IC10-LDQM)") (class "Default")
      (node (ref "IC10") (pin "15") (pinfunction "LDQM_15") (pintype "input"))
      (node (ref "IC10") (pin "39") (pinfunction "UDQM_39") (pintype "input"))
      (node (ref "IC12") (pin "4") (pinfunction "Y_4") (pintype "output"))
    )
    (net (code "102") (name "Net-(IC10-~{CS})") (class "Default")
      (node (ref "IC10") (pin "19") (pinfunction "~{CS}_19") (pintype "input"))
      (node (ref "R15") (pin "1") (pinfunction "1_1") (pintype "passive"))
    )
    (net (code "103") (name "Net-(IC17-SW)") (class "Default")
      (node (ref "C34") (pin "1") (pinfunction "1_1") (pintype "passive"))
      (node (ref "IC17") (pin "2") (pinfunction "SW_2") (pintype "output"))
      (node (ref "L4") (pin "1") (pinfunction "1_1") (pintype "passive"))
    )
    (net (code "104") (name "Net-(IC17-VBST)") (class "Default")
      (node (ref "C34") (pin "2") (pinfunction "2_2") (pintype "passive"))
      (node (ref "IC17") (pin "6") (pinfunction "VBST_6") (pintype "passive"))
    )
    (net (code "105") (name "Net-(IC17-VFB)") (class "Default")
      (node (ref "IC17") (pin "4") (pinfunction "VFB_4") (pintype "passive"))
      (node (ref "R23") (pin "1") (pinfunction "1_1") (pintype "passive"))
      (node (ref "R24") (pin "2") (pinfunction "2_2") (pintype "passive"))
    )
    (net (code "106") (name "Net-(IC18A-PLL_AVDD)") (class "Default")
      (node (ref "C57") (pin "1") (pinfunction "1_1") (pintype "passive"))
      (node (ref "IC18") (pin "103") (pinfunction "PLL_AVDD_103") (pintype "power_in"))
      (node (ref "R31") (pin "2") (pinfunction "2_2") (pintype "passive"))
    )
    (net (code "107") (name "Net-(IC18B-CLK)") (class "Default")
      (node (ref "IC18") (pin "125") (pinfunction "CLK_125") (pintype "passive"))
      (node (ref "R25") (pin "2") (pinfunction "2_2") (pintype "passive"))
    )
    (net (code "108") (name "Net-(IC18B-TCK)") (class "Default")
      (node (ref "IC18") (pin "128") (pinfunction "TCK_128") (pintype "passive"))
      (node (ref "R30") (pin "1") (pinfunction "1_1") (pintype "passive"))
    )
    (net (code "109") (name "Net-(IC18B-TMS)") (class "Default")
      (node (ref "IC18") (pin "127") (pinfunction "TMS_127") (pintype "passive"))
      (node (ref "R29") (pin "1") (pinfunction "1_1") (pintype "passive"))
    )
    (net (code "110") (name "Net-(IC18C-X0D42)") (class "Default")
      (node (ref "IC18") (pin "10") (pinfunction "X0D42_10") (pintype "bidirectional"))
      (node (ref "R27") (pin "1") (pinfunction "1_1") (pintype "passive"))
    )
    (net (code "111") (name "Net-(IC18C-X0D43)") (class "Default")
      (node (ref "IC18") (pin "12") (pinfunction "X0D43_12") (pintype "bidirectional"))
      (node (ref "R28") (pin "1") (pinfunction "1_1") (pintype "passive"))
    )
    (net (code "112") (name "Net-(IC18D-X1D26)") (class "Default")
      (node (ref "IC18") (pin "112") (pinfunction "X1D26_112") (pintype "bidirectional"))
      (node (ref "R42") (pin "1") (pinfunction "1_1") (pintype "passive"))
    )
    (net (code "113") (name "Net-(IC18E-USB_ID)") (class "Default")
      (node (ref "IC18") (pin "43") (pinfunction "USB_ID_43") (pintype "passive"))
      (node (ref "R67") (pin "1") (pinfunction "1_1") (pintype "passive"))
    )
    (net (code "114") (name "Net-(IC18E-USB_RTUNE)") (class "Default")
      (node (ref "IC18") (pin "48") (pinfunction "USB_RTUNE_48") (pintype "passive"))
      (node (ref "R22") (pin "1") (pinfunction "1_1") (pintype "passive"))
    )
    (net (code "115") (name "Net-(IC18E-USB_VBUS)") (class "Default")
      (node (ref "C31") (pin "1") (pinfunction "1_1") (pintype "passive"))
      (node (ref "IC18") (pin "45") (pinfunction "USB_VBUS_45") (pintype "passive"))
      (node (ref "R18") (pin "2") (pinfunction "2_2") (pintype "passive"))
    )
    (net (code "116") (name "Net-(IC22A-Y)") (class "Default")
      (node (ref "C60") (pin "1") (pinfunction "1_1") (pintype "passive"))
      (node (ref "IC22") (pin "4") (pinfunction "Y_4") (pintype "output"))
      (node (ref "R33") (pin "2") (pinfunction "2_2") (pintype "passive"))
    )
    (net (code "117") (name "Net-(IC23-BYPASS)") (class "Default")
      (node (ref "C64") (pin "2") (pinfunction "2_2") (pintype "passive"))
      (node (ref "IC23") (pin "2") (pinfunction "BYPASS_2") (pintype "input"))
    )
    (net (code "118") (name "Net-(IC23-IN+)") (class "Default")
      (node (ref "IC23") (pin "3") (pinfunction "IN+_3") (pintype "input"))
      (node (ref "R32") (pin "2") (pinfunction "2_2") (pintype "passive"))
      (node (ref "R35") (pin "1") (pinfunction "1_1") (pintype "passive"))
    )
    (net (code "119") (name "Net-(IC23-IN-)") (class "Default")
      (node (ref "IC23") (pin "4") (pinfunction "IN-_4") (pintype "input"))
      (node (ref "R36") (pin "1") (pinfunction "1_1") (pintype "passive"))
      (node (ref "R38") (pin "2") (pinfunction "2_2") (pintype "passive"))
    )
    (net (code "120") (name "Net-(IC23-VO+)") (class "Default")
      (node (ref "IC23") (pin "5") (pinfunction "VO+_5") (pintype "output"))
      (node (ref "R38") (pin "1") (pinfunction "1_1") (pintype "passive"))
      (node (ref "SP1") (pin "+") (pinfunction "+_+") (pintype "passive"))
      (node (ref "X6") (pin "2") (pinfunction "S_2") (pintype "passive"))
    )
    (net (code "121") (name "Net-(IC23-VO-)") (class "Default")
      (node (ref "IC23") (pin "8") (pinfunction "VO-_8") (pintype "output"))
      (node (ref "R32") (pin "1") (pinfunction "1_1") (pintype "passive"))
      (node (ref "SP1") (pin "-") (pinfunction "-_-") (pintype "passive"))
      (node (ref "X6") (pin "1") (pinfunction "S_1") (pintype "passive"))
    )
    (net (code "122") (name "Net-(IC24-PFBIN1)") (class "Default")
      (node (ref "C69") (pin "1") (pinfunction "1_1") (pintype "passive"))
      (node (ref "C70") (pin "1") (pinfunction "1_1") (pintype "passive"))
      (node (ref "C71") (pin "+") (pinfunction "+_+") (pintype "passive"))
      (node (ref "C72") (pin "1") (pinfunction "1_1") (pintype "passive"))
      (node (ref "IC24") (pin "18") (pinfunction "PFBIN1_18") (pintype "input"))
      (node (ref "IC24") (pin "23") (pinfunction "PFBOUT_23") (pintype "output"))
      (node (ref "IC24") (pin "37") (pinfunction "PFBIN2_37") (pintype "input"))
    )
    (net (code "123") (name "Net-(IC24-RBIAS)") (class "Default")
      (node (ref "IC24") (pin "24") (pinfunction "RBIAS_24") (pintype "input"))
      (node (ref "R53") (pin "2") (pinfunction "2_2") (pintype "passive"))
    )
    (net (code "124") (name "Net-(IC24-RD+)") (class "Default")
      (node (ref "IC24") (pin "14") (pinfunction "RD+_14") (pintype "bidirectional"))
      (node (ref "R44") (pin "2") (pinfunction "2_2") (pintype "passive"))
      (node (ref "X7") (pin "7") (pinfunction "RD+_7") (pintype "input"))
    )
    (net (code "125") (name "Net-(IC24-RD-)") (class "Default")
      (node (ref "IC24") (pin "13") (pinfunction "RD-_13") (pintype "bidirectional"))
      (node (ref "R47") (pin "1") (pinfunction "1_1") (pintype "passive"))
      (node (ref "X7") (pin "8") (pinfunction "RD-_8") (pintype "input"))
    )
    (net (code "126") (name "Net-(IC24-RESERVED-20)") (class "Default")
      (node (ref "IC24") (pin "20") (pinfunction "RESERVED-20_20") (pintype "bidirectional"))
      (node (ref "R52") (pin "2") (pinfunction "2_2") (pintype "passive"))
    )
    (net (code "127") (name "Net-(IC24-RESERVED-21)") (class "Default")
      (node (ref "IC24") (pin "21") (pinfunction "RESERVED-21_21") (pintype "bidirectional"))
      (node (ref "R51") (pin "2") (pinfunction "2_2") (pintype "passive"))
    )
    (net (code "128") (name "Net-(IC24-TD+)") (class "Default")
      (node (ref "IC24") (pin "17") (pinfunction "TD+_17") (pintype "bidirectional"))
      (node (ref "R40") (pin "2") (pinfunction "2_2") (pintype "passive"))
      (node (ref "X7") (pin "1") (pinfunction "TD+_1") (pintype "input"))
    )
    (net (code "129") (name "Net-(IC24-TD-)") (class "Default")
      (node (ref "IC24") (pin "16") (pinfunction "TD-_16") (pintype "bidirectional"))
      (node (ref "R41") (pin "1") (pinfunction "1_1") (pintype "passive"))
      (node (ref "X7") (pin "2") (pinfunction "TD-_2") (pintype "input"))
    )
    (net (code "130") (name "Net-(IC24-X1)") (class "Default")
      (node (ref "IC24") (pin "34") (pinfunction "X1_34") (pintype "input"))
      (node (ref "R39") (pin "2") (pinfunction "2_2") (pintype "passive"))
    )
    (net (code "131") (name "Net-(IC27-OSCI)") (class "Default")
      (node (ref "IC27") (pin "1") (pinfunction "OSCI_1") (pintype "input"))
      (node (ref "Y1") (pin "1") (pinfunction "1_1") (pintype "passive"))
    )
    (net (code "132") (name "Net-(IC27-OSCO)") (class "Default")
      (node (ref "IC27") (pin "2") (pinfunction "OSCO_2") (pintype "output"))
      (node (ref "Y1") (pin "4") (pinfunction "2_4") (pintype "passive"))
    )
    (net (code "133") (name "Net-(IC27-VDD)") (class "Default")
      (node (ref "C78") (pin "2") (pinfunction "2_2") (pintype "passive"))
      (node (ref "D2") (pin "C") (pinfunction "C_C") (pintype "passive"))
      (node (ref "IC27") (pin "14") (pinfunction "VDD_14") (pintype "power_in"))
      (node (ref "R54") (pin "2") (pinfunction "2_2") (pintype "passive"))
    )
    (net (code "134") (name "Net-(LCD1-DISP)") (class "Default")
      (node (ref "LCD1") (pin "31") (pinfunction "DISP_31") (pintype "input"))
      (node (ref "R7") (pin "1") (pinfunction "1_1") (pintype "passive"))
    )
    (net (code "135") (name "Net-(LCD1-RESET)") (class "Default")
      (node (ref "JP1") (pin "2") (pinfunction "2_2") (pintype "passive"))
      (node (ref "LCD1") (pin "36") (pinfunction "RESET_36") (pintype "input"))
    )
    (net (code "136") (name "Net-(LED1-PadC)") (class "Default")
      (node (ref "LED1") (pin "C") (pinfunction "C_C") (pintype "passive"))
      (node (ref "R55") (pin "2") (pinfunction "2_2") (pintype "passive"))
    )
    (net (code "137") (name "Net-(LED2-PadC)") (class "Default")
      (node (ref "LED2") (pin "C") (pinfunction "C_C") (pintype "passive"))
      (node (ref "R56") (pin "2") (pinfunction "2_2") (pintype "passive"))
    )
    (net (code "138") (name "Net-(LED3-PadC)") (class "Default")
      (node (ref "LED3") (pin "C") (pinfunction "C_C") (pintype "passive"))
      (node (ref "R57") (pin "2") (pinfunction "2_2") (pintype "passive"))
    )
    (net (code "139") (name "Net-(OK1A-A)") (class "Default")
      (node (ref "OK1") (pin "1") (pinfunction "A_1") (pintype "passive"))
      (node (ref "R61") (pin "1") (pinfunction "1_1") (pintype "passive"))
    )
    (net (code "140") (name "Net-(OK1A-COL)") (class "Default")
      (node (ref "OK1") (pin "8") (pinfunction "COL_8") (pintype "passive"))
      (node (ref "X8") (pin "10") (pinfunction "1_10") (pintype "passive"))
      (node (ref "ZD7") (pin "C") (pinfunction "C_C") (pintype "passive"))
    )
    (net (code "141") (name "Net-(OK1A-EMIT)") (class "Default")
      (node (ref "OK1") (pin "7") (pinfunction "EMIT_7") (pintype "passive"))
      (node (ref "X8") (pin "9") (pinfunction "1_9") (pintype "passive"))
      (node (ref "ZD7") (pin "A") (pinfunction "A_A") (pintype "passive"))
    )
    (net (code "142") (name "Net-(OK1B-A)") (class "Default")
      (node (ref "OK1") (pin "3") (pinfunction "A_3") (pintype "passive"))
      (node (ref "R62") (pin "1") (pinfunction "1_1") (pintype "passive"))
    )
    (net (code "143") (name "Net-(OK1B-COL)") (class "Default")
      (node (ref "OK1") (pin "6") (pinfunction "COL_6") (pintype "passive"))
      (node (ref "X8") (pin "8") (pinfunction "1_8") (pintype "passive"))
      (node (ref "ZD8") (pin "C") (pinfunction "C_C") (pintype "passive"))
    )
    (net (code "144") (name "Net-(OK1B-EMIT)") (class "Default")
      (node (ref "OK1") (pin "5") (pinfunction "EMIT_5") (pintype "passive"))
      (node (ref "X8") (pin "7") (pinfunction "1_7") (pintype "passive"))
      (node (ref "ZD8") (pin "A") (pinfunction "A_A") (pintype "passive"))
    )
    (net (code "145") (name "Net-(OK2A-A)") (class "Default")
      (node (ref "D3") (pin "C") (pinfunction "C_C") (pintype "passive"))
      (node (ref "OK2") (pin "1") (pinfunction "A_1") (pintype "passive"))
    )
    (net (code "146") (name "Net-(OK2A-C)") (class "Default")
      (node (ref "OK2") (pin "2") (pinfunction "C_2") (pintype "passive"))
      (node (ref "X8") (pin "11") (pinfunction "1_11") (pintype "passive"))
    )
    (net (code "147") (name "Net-(OK2B-A)") (class "Default")
      (node (ref "D4") (pin "C") (pinfunction "C_C") (pintype "passive"))
      (node (ref "OK2") (pin "3") (pinfunction "A_3") (pintype "passive"))
    )
    (net (code "148") (name "Net-(OK2B-C)") (class "Default")
      (node (ref "OK2") (pin "4") (pinfunction "C_4") (pintype "passive"))
      (node (ref "X8") (pin "13") (pinfunction "1_13") (pintype "passive"))
    )
    (net (code "149") (name "Net-(PWR_3V3-PadC)") (class "Default")
      (node (ref "PWR_3V3") (pin "C") (pinfunction "C_C") (pintype "passive"))
      (node (ref "R5") (pin "2") (pinfunction "2_2") (pintype "passive"))
    )
    (net (code "150") (name "Net-(Q1-G)") (class "Default")
      (node (ref "Q1") (pin "1") (pinfunction "G_1") (pintype "passive"))
      (node (ref "R2") (pin "2") (pinfunction "2_2") (pintype "passive"))
      (node (ref "ZD2") (pin "A") (pinfunction "A_A") (pintype "passive"))
    )
    (net (code "151") (name "Net-(R45-Pad2)") (class "Default")
      (node (ref "R45") (pin "2") (pinfunction "2_2") (pintype "passive"))
      (node (ref "SPEED") (pin "A") (pinfunction "A_A") (pintype "passive"))
    )
    (net (code "152") (name "Net-(R58-Pad1)") (class "Default")
      (node (ref "R58") (pin "1") (pinfunction "1_1") (pintype "passive"))
      (node (ref "X8") (pin "1") (pinfunction "1_1") (pintype "passive"))
    )
    (net (code "153") (name "Net-(X3D-1)") (class "Default")
      (node (ref "R17") (pin "1") (pinfunction "1_1") (pintype "passive"))
      (node (ref "X3") (pin "4") (pinfunction "1_4") (pintype "passive"))
    )
    (net (code "154") (name "Net-(X7-GREEN-C)") (class "Default")
      (node (ref "R50") (pin "1") (pinfunction "1_1") (pintype "passive"))
      (node (ref "X7") (pin "10") (pinfunction "GREEN-C_10") (pintype "passive"))
    )
    (net (code "155") (name "Net-(X7-YELLOW-C)") (class "Default")
      (node (ref "R49") (pin "1") (pinfunction "1_1") (pintype "passive"))
      (node (ref "X7") (pin "11") (pinfunction "YELLOW-C_11") (pintype "passive"))
    )
    (net (code "156") (name "Net-(X8D-1)") (class "Default")
      (node (ref "R63") (pin "1") (pinfunction "1_1") (pintype "passive"))
      (node (ref "X8") (pin "12") (pinfunction "1_12") (pintype "passive"))
    )
    (net (code "157") (name "Net-(X8F-1)") (class "Default")
      (node (ref "R64") (pin "1") (pinfunction "1_1") (pintype "passive"))
      (node (ref "X8") (pin "14") (pinfunction "1_14") (pintype "passive"))
    )
    (net (code "158") (name "Net-(X8H-1)") (class "Default")
      (node (ref "R59") (pin "1") (pinfunction "1_1") (pintype "passive"))
      (node (ref "X8") (pin "3") (pinfunction "1_3") (pintype "passive"))
    )
    (net (code "159") (name "Net-(X8J-1)") (class "Default")
      (node (ref "R60") (pin "1") (pinfunction "1_1") (pintype "passive"))
      (node (ref "X8") (pin "5") (pinfunction "1_5") (pintype "passive"))
    )
    (net (code "160") (name "Net-(XO1-OUT)") (class "Default")
      (node (ref "R25") (pin "1") (pinfunction "1_1") (pintype "passive"))
      (node (ref "XO1") (pin "3") (pinfunction "OUT_3") (pintype "output"))
    )
    (net (code "161") (name "Net-(XO2-OUT)") (class "Default")
      (node (ref "R39") (pin "1") (pinfunction "1_1") (pintype "passive"))
      (node (ref "XO2") (pin "3") (pinfunction "OUT_3") (pintype "output"))
    )
    (net (code "162") (name "QSPI_CLK") (class "Default")
      (node (ref "IC11") (pin "5") (pinfunction "2B1_5") (pintype "passive"))
      (node (ref "IC13") (pin "6") (pinfunction "SCK_6") (pintype "input"))
      (node (ref "X2") (pin "9") (pinfunction "1_9") (pintype "passive"))
    )
    (net (code "163") (name "QSPI_D0") (class "Default")
      (node (ref "IC13") (pin "5") (pinfunction "SI/IO0_5") (pintype "bidirectional"))
      (node (ref "IC14") (pin "2") (pinfunction "1B1_2") (pintype "passive"))
      (node (ref "X2") (pin "8") (pinfunction "1_8") (pintype "passive"))
    )
    (net (code "164") (name "QSPI_D1") (class "Default")
      (node (ref "IC13") (pin "2") (pinfunction "SO/IO1_2") (pintype "bidirectional"))
      (node (ref "IC14") (pin "5") (pinfunction "2B1_5") (pintype "passive"))
      (node (ref "X2") (pin "7") (pinfunction "1_7") (pintype "passive"))
    )
    (net (code "165") (name "QSPI_D2") (class "Default")
      (node (ref "IC13") (pin "3") (pinfunction "~{WP}/IO2_3") (pintype "bidirectional"))
      (node (ref "IC14") (pin "11") (pinfunction "3B1_11") (pintype "passive"))
      (node (ref "X2") (pin "6") (pinfunction "1_6") (pintype "passive"))
    )
    (net (code "166") (name "QSPI_D3") (class "Default")
      (node (ref "IC13") (pin "7") (pinfunction "~{HOLD}/IO3_7") (pintype "bidirectional"))
      (node (ref "IC14") (pin "14") (pinfunction "4B1_14") (pintype "passive"))
      (node (ref "X2") (pin "5") (pinfunction "1_5") (pintype "passive"))
    )
    (net (code "167") (name "SD_ADQ0") (class "Default")
      (node (ref "IC10") (pin "2") (pinfunction "DQ0_2") (pintype "bidirectional"))
      (node (ref "IC10") (pin "23") (pinfunction "A0_23") (pintype "input"))
      (node (ref "IC18") (pin "37") (pinfunction "X0D02_37") (pintype "bidirectional"))
    )
    (net (code "168") (name "SD_ADQ1") (class "Default")
      (node (ref "IC10") (pin "24") (pinfunction "A1_24") (pintype "input"))
      (node (ref "IC10") (pin "4") (pinfunction "DQ1_4") (pintype "bidirectional"))
      (node (ref "IC18") (pin "38") (pinfunction "X0D03_38") (pintype "bidirectional"))
    )
    (net (code "169") (name "SD_ADQ2") (class "Default")
      (node (ref "IC10") (pin "25") (pinfunction "A2_25") (pintype "input"))
      (node (ref "IC10") (pin "5") (pinfunction "DQ2_5") (pintype "bidirectional"))
      (node (ref "IC14") (pin "3") (pinfunction "1B2_3") (pintype "passive"))
    )
    (net (code "170") (name "SD_ADQ3") (class "Default")
      (node (ref "IC10") (pin "26") (pinfunction "A3_26") (pintype "input"))
      (node (ref "IC10") (pin "7") (pinfunction "DQ3_7") (pintype "bidirectional"))
      (node (ref "IC14") (pin "6") (pinfunction "2B2_6") (pintype "passive"))
    )
    (net (code "171") (name "SD_ADQ4") (class "Default")
      (node (ref "IC10") (pin "29") (pinfunction "A4_29") (pintype "input"))
      (node (ref "IC10") (pin "8") (pinfunction "DQ4_8") (pintype "bidirectional"))
      (node (ref "IC14") (pin "10") (pinfunction "3B2_10") (pintype "passive"))
    )
    (net (code "172") (name "SD_ADQ5") (class "Default")
      (node (ref "IC10") (pin "10") (pinfunction "DQ5_10") (pintype "bidirectional"))
      (node (ref "IC10") (pin "30") (pinfunction "A5_30") (pintype "input"))
      (node (ref "IC14") (pin "13") (pinfunction "4B2_13") (pintype "passive"))
    )
    (net (code "173") (name "SD_ADQ6") (class "Default")
      (node (ref "IC10") (pin "11") (pinfunction "DQ6_11") (pintype "bidirectional"))
      (node (ref "IC10") (pin "31") (pinfunction "A6_31") (pintype "input"))
      (node (ref "IC18") (pin "39") (pinfunction "X0D08_39") (pintype "bidirectional"))
    )
    (net (code "174") (name "SD_ADQ7") (class "Default")
      (node (ref "IC10") (pin "13") (pinfunction "DQ7_13") (pintype "bidirectional"))
      (node (ref "IC10") (pin "32") (pinfunction "A7_32") (pintype "input"))
      (node (ref "IC18") (pin "40") (pinfunction "X0D09_40") (pintype "bidirectional"))
    )
    (net (code "175") (name "SD_ADQ8") (class "Default")
      (node (ref "IC10") (pin "33") (pinfunction "A8_33") (pintype "input"))
      (node (ref "IC10") (pin "42") (pinfunction "DQ8_42") (pintype "bidirectional"))
      (node (ref "IC18") (pin "57") (pinfunction "X0D14_57") (pintype "bidirectional"))
    )
    (net (code "176") (name "SD_ADQ9") (class "Default")
      (node (ref "IC10") (pin "34") (pinfunction "A9_34") (pintype "input"))
      (node (ref "IC10") (pin "44") (pinfunction "DQ9_44") (pintype "bidirectional"))
      (node (ref "IC18") (pin "58") (pinfunction "X0D15_58") (pintype "bidirectional"))
    )
    (net (code "177") (name "SD_ADQ10") (class "Default")
      (node (ref "IC10") (pin "22") (pinfunction "A10/AP_22") (pintype "input"))
      (node (ref "IC10") (pin "45") (pinfunction "DQ10_45") (pintype "bidirectional"))
      (node (ref "IC18") (pin "68") (pinfunction "X0D16_68") (pintype "bidirectional"))
    )
    (net (code "178") (name "SD_ADQ11") (class "Default")
      (node (ref "IC10") (pin "35") (pinfunction "A11_35") (pintype "input"))
      (node (ref "IC10") (pin "47") (pinfunction "DQ11_47") (pintype "bidirectional"))
      (node (ref "IC18") (pin "69") (pinfunction "X0D17_69") (pintype "bidirectional"))
    )
    (net (code "179") (name "SD_ADQ12") (class "Default")
      (node (ref "IC10") (pin "36") (pinfunction "A12/NC-36_36") (pintype "passive"))
      (node (ref "IC10") (pin "48") (pinfunction "DQ12_48") (pintype "bidirectional"))
      (node (ref "IC18") (pin "70") (pinfunction "X0D18_70") (pintype "bidirectional"))
    )
    (net (code "180") (name "SD_ADQ13") (class "Default")
      (node (ref "IC10") (pin "20") (pinfunction "BA0_20") (pintype "input"))
      (node (ref "IC10") (pin "50") (pinfunction "DQ13_50") (pintype "bidirectional"))
      (node (ref "IC18") (pin "71") (pinfunction "X0D19_71") (pintype "bidirectional"))
    )
    (net (code "181") (name "SD_ADQ14") (class "Default")
      (node (ref "IC10") (pin "21") (pinfunction "BA1_21") (pintype "input"))
      (node (ref "IC10") (pin "51") (pinfunction "DQ14_51") (pintype "bidirectional"))
      (node (ref "IC18") (pin "59") (pinfunction "X0D20_59") (pintype "bidirectional"))
    )
    (net (code "182") (name "SD_ADQ15") (class "Default")
      (node (ref "IC10") (pin "53") (pinfunction "DQ15_53") (pintype "bidirectional"))
      (node (ref "IC18") (pin "61") (pinfunction "X0D21_61") (pintype "bidirectional"))
    )
    (net (code "183") (name "SD_CLK") (class "Default")
      (node (ref "IC10") (pin "38") (pinfunction "CLK_38") (pintype "input"))
      (node (ref "IC18") (pin "63") (pinfunction "X0D13_63") (pintype "bidirectional"))
    )
    (net (code "184") (name "SPI0_CLK") (class "Default")
      (node (ref "IC18") (pin "100") (pinfunction "X0D31_100") (pintype "bidirectional"))
      (node (ref "IC3") (pin "11") (pinfunction "SRCLK_11") (pintype "input"))
      (node (ref "IC5") (pin "11") (pinfunction "SRCLK_11") (pintype "input"))
    )
    (net (code "185") (name "SPI0_MOSI") (class "Default")
      (node (ref "IC18") (pin "93") (pinfunction "X0D26_93") (pintype "bidirectional"))
      (node (ref "IC3") (pin "14") (pinfunction "SER_14") (pintype "input"))
    )
    (net (code "186") (name "SPI0_STROBE") (class "Default")
      (node (ref "IC18") (pin "95") (pinfunction "X0D32_95") (pintype "bidirectional"))
      (node (ref "IC3") (pin "12") (pinfunction "RCLK_12") (pintype "input"))
      (node (ref "IC5") (pin "12") (pinfunction "RCLK_12") (pintype "input"))
    )
    (net (code "187") (name "SPI1_CLK") (class "Default")
      (node (ref "IC18") (pin "94") (pinfunction "X0D27_94") (pintype "bidirectional"))
      (node (ref "IC26") (pin "11") (pinfunction "SRCLK_11") (pintype "input"))
      (node (ref "IC27") (pin "10") (pinfunction "SCL_10") (pintype "bidirectional"))
      (node (ref "IC28") (pin "12") (pinfunction "SCK_12") (pintype "input"))
      (node (ref "IC29") (pin "6") (pinfunction "SCK_6") (pintype "input"))
      (node (ref "IC7") (pin "11") (pinfunction "SCK/SCL/TX_11") (pintype "bidirectional"))
      (node (ref "J2") (pin "5") (pinfunction "CLK_5") (pintype "passive"))
      (node (ref "MOD1") (pin "5") (pinfunction "SCLK_5") (pintype "input"))
    )
    (net (code "188") (name "SPI1_MISO") (class "Default")
      (node (ref "IC18") (pin "91") (pinfunction "X0D35_91") (pintype "bidirectional"))
      (node (ref "IC27") (pin "8") (pinfunction "SDO_8") (pintype "passive"))
      (node (ref "IC28") (pin "14") (pinfunction "SO_14") (pintype "passive"))
      (node (ref "IC29") (pin "2") (pinfunction "SO_2") (pintype "output"))
      (node (ref "IC7") (pin "9") (pinfunction "SDO_9") (pintype "bidirectional"))
      (node (ref "J2") (pin "7") (pinfunction "DAT0_7") (pintype "passive"))
      (node (ref "MOD1") (pin "2") (pinfunction "MISO_2") (pintype "passive"))
    )
    (net (code "189") (name "SPI1_MOSI") (class "Default")
      (node (ref "IC18") (pin "99") (pinfunction "X0D30_99") (pintype "bidirectional"))
      (node (ref "IC26") (pin "14") (pinfunction "SER_14") (pintype "input"))
      (node (ref "IC27") (pin "9") (pinfunction "SDI_9") (pintype "input"))
      (node (ref "IC28") (pin "13") (pinfunction "SI_13") (pintype "input"))
      (node (ref "IC29") (pin "5") (pinfunction "SI_5") (pintype "input"))
      (node (ref "IC7") (pin "13") (pinfunction "SDI/SDA/RX_13") (pintype "bidirectional"))
      (node (ref "J2") (pin "3") (pinfunction "CMD_3") (pintype "passive"))
      (node (ref "MOD1") (pin "3") (pinfunction "MOSI_3") (pintype "passive"))
    )
    (net (code "190") (name "SPI1_SELECT") (class "Default")
      (node (ref "IC18") (pin "97") (pinfunction "X0D33_97") (pintype "bidirectional"))
      (node (ref "IC26") (pin "12") (pinfunction "RCLK_12") (pintype "input"))
    )
    (net (code "191") (name "SPI2_CLK") (class "Default")
      (node (ref "IC18") (pin "96") (pinfunction "X0D28_96") (pintype "bidirectional"))
      (node (ref "X9") (pin "3") (pinfunction "1_3") (pintype "passive"))
    )
    (net (code "192") (name "SPI2_MISO") (class "Default")
      (node (ref "IC18") (pin "3") (pinfunction "X0D36_3") (pintype "bidirectional"))
      (node (ref "X9") (pin "4") (pinfunction "1_4") (pintype "passive"))
    )
    (net (code "193") (name "SPI2_MOSI") (class "Default")
      (node (ref "IC18") (pin "98") (pinfunction "X0D29_98") (pintype "bidirectional"))
      (node (ref "X9") (pin "5") (pinfunction "1_5") (pintype "passive"))
    )
    (net (code "194") (name "SPI2_SELECT") (class "Default")
      (node (ref "IC18") (pin "90") (pinfunction "X0D34_90") (pintype "bidirectional"))
      (node (ref "X9") (pin "6") (pinfunction "1_6") (pintype "passive"))
    )
    (net (code "195") (name "SPI_INT") (class "Default")
      (node (ref "IC18") (pin "13") (pinfunction "X1D35_13") (pintype "bidirectional"))
      (node (ref "IC28") (pin "19") (pinfunction "INTB_19") (pintype "passive"))
      (node (ref "IC28") (pin "20") (pinfunction "INTA_20") (pintype "passive"))
    )
    (net (code "196") (name "TCK") (class "Default")
      (node (ref "IC19") (pin "5") (pinfunction "IO4_5") (pintype "bidirectional"))
      (node (ref "R30") (pin "2") (pinfunction "2_2") (pintype "passive"))
      (node (ref "X5") (pin "9") (pinfunction "9_9") (pintype "passive"))
    )
    (net (code "197") (name "TDI") (class "Default")
      (node (ref "IC18") (pin "2") (pinfunction "TDI_2") (pintype "passive"))
      (node (ref "IC19") (pin "1") (pinfunction "IO1_1") (pintype "bidirectional"))
      (node (ref "X5") (pin "5") (pinfunction "5_5") (pintype "passive"))
    )
    (net (code "198") (name "TDO") (class "Default")
      (node (ref "IC18") (pin "1") (pinfunction "TDO_1") (pintype "passive"))
      (node (ref "IC19") (pin "4") (pinfunction "IO3_4") (pintype "bidirectional"))
      (node (ref "X5") (pin "13") (pinfunction "13_13") (pintype "passive"))
    )
    (net (code "199") (name "TMS") (class "Default")
      (node (ref "IC19") (pin "2") (pinfunction "IO2_2") (pintype "bidirectional"))
      (node (ref "R29") (pin "2") (pinfunction "2_2") (pintype "passive"))
      (node (ref "X5") (pin "7") (pinfunction "7_7") (pintype "passive"))
    )
    (net (code "200") (name "TRST_N") (class "Default")
      (node (ref "IC21") (pin "2") (pinfunction "A_2") (pintype "input"))
      (node (ref "R26") (pin "2") (pinfunction "2_2") (pintype "passive"))
      (node (ref "X5") (pin "15") (pinfunction "15_15") (pintype "passive"))
    )
    (net (code "201") (name "USB_D_N") (class "Default")
      (node (ref "IC16") (pin "2") (pinfunction "IO1_2") (pintype "bidirectional"))
      (node (ref "IC18") (pin "47") (pinfunction "USB_DM_47") (pintype "passive"))
      (node (ref "J1") (pin "2") (pinfunction "D-_2") (pintype "passive"))
    )
    (net (code "202") (name "USB_D_P") (class "Default")
      (node (ref "IC16") (pin "3") (pinfunction "IO2_3") (pintype "bidirectional"))
      (node (ref "IC18") (pin "46") (pinfunction "USB_DP_46") (pintype "passive"))
      (node (ref "J1") (pin "3") (pinfunction "D+_3") (pintype "passive"))
    )
    (net (code "203") (name "USB_ID") (class "Default")
      (node (ref "IC28") (pin "8") (pinfunction "GPB7_8") (pintype "bidirectional"))
      (node (ref "J1") (pin "4") (pinfunction "ID_4") (pintype "passive"))
      (node (ref "R20") (pin "2") (pinfunction "2_2") (pintype "passive"))
    )
    (net (code "204") (name "USB_VBUS") (class "Default")
      (node (ref "C32") (pin "1") (pinfunction "1_1") (pintype "passive"))
      (node (ref "C33") (pin "2") (pinfunction "2_2") (pintype "passive"))
      (node (ref "FB1") (pin "P$1") (pinfunction "1_P$1") (pintype "passive"))
      (node (ref "IC15") (pin "1") (pinfunction "OUT_1") (pintype "output"))
      (node (ref "IC16") (pin "4") (pinfunction "VCC_4") (pintype "power_in"))
      (node (ref "R18") (pin "1") (pinfunction "1_1") (pintype "passive"))
      (node (ref "R21") (pin "1") (pinfunction "1_1") (pintype "passive"))
    )
    (net (code "205") (name "VBUS_EN") (class "Default")
      (node (ref "IC15") (pin "4") (pinfunction "EN_4") (pintype "input"))
      (node (ref "IC17") (pin "5") (pinfunction "EN_5") (pintype "input"))
      (node (ref "IC26") (pin "7") (pinfunction "Q7/H_7") (pintype "output"))
    )
    (net (code "206") (name "VIN") (class "Default")
      (node (ref "C4") (pin "1") (pinfunction "1_1") (pintype "passive"))
      (node (ref "C40") (pin "1") (pinfunction "1_1") (pintype "passive"))
      (node (ref "C8") (pin "1") (pinfunction "1_1") (pintype "passive"))
      (node (ref "IC17") (pin "3") (pinfunction "VIN_3") (pintype "input"))
      (node (ref "IC2") (pin "3") (pinfunction "VIN_3") (pintype "input"))
      (node (ref "IC2") (pin "5") (pinfunction "EN_5") (pintype "input"))
      (node (ref "IC4") (pin "3") (pinfunction "VIN_3") (pintype "input"))
      (node (ref "Q1") (pin "2") (pinfunction "S_2") (pintype "passive"))
      (node (ref "ZD2") (pin "C") (pinfunction "C_C") (pintype "passive"))
    )
    (net (code "207") (name "VLED+") (class "Default")
      (node (ref "C1") (pin "1") (pinfunction "1_1") (pintype "passive"))
      (node (ref "D1") (pin "C") (pinfunction "C_C") (pintype "passive"))
      (node (ref "LCD1") (pin "2") (pinfunction "VLED+_2") (pintype "power_in"))
    )
    (net (code "208") (name "VLED-") (class "Default")
      (node (ref "IC1") (pin "3") (pinfunction "FB_3") (pintype "input"))
      (node (ref "LCD1") (pin "1") (pinfunction "VLED-_1") (pintype "power_in"))
      (node (ref "R3") (pin "1") (pinfunction "1_1") (pintype "passive"))
    )
    (net (code "209") (name "X0D00{slash}LATCH") (class "Default")
      (node (ref "IC18") (pin "30") (pinfunction "X0D00_30") (pintype "bidirectional"))
      (node (ref "X3") (pin "1") (pinfunction "1_1") (pintype "passive"))
    )
    (net (code "210") (name "X0D01{slash}~{QS_CS}") (class "Default")
      (node (ref "IC11") (pin "4") (pinfunction "1A_4") (pintype "passive"))
      (node (ref "IC18") (pin "27") (pinfunction "X0D01_27") (pintype "bidirectional"))
    )
    (net (code "211") (name "X0D04{slash}QS_D0") (class "Default")
      (node (ref "IC14") (pin "4") (pinfunction "1A_4") (pintype "passive"))
      (node (ref "IC18") (pin "31") (pinfunction "X0D04_31") (pintype "bidirectional"))
    )
    (net (code "212") (name "X0D05{slash}QS_D1") (class "Default")
      (node (ref "IC14") (pin "7") (pinfunction "2A_7") (pintype "passive"))
      (node (ref "IC18") (pin "33") (pinfunction "X0D05_33") (pintype "bidirectional"))
      (node (ref "X3") (pin "5") (pinfunction "1_5") (pintype "passive"))
    )
    (net (code "213") (name "X0D06{slash}QS_D2") (class "Default")
      (node (ref "IC14") (pin "9") (pinfunction "3A_9") (pintype "passive"))
      (node (ref "IC18") (pin "34") (pinfunction "X0D06_34") (pintype "bidirectional"))
    )
    (net (code "214") (name "X0D07{slash}QS_D3") (class "Default")
      (node (ref "IC14") (pin "12") (pinfunction "4A_12") (pintype "passive"))
      (node (ref "IC18") (pin "35") (pinfunction "X0D07_35") (pintype "bidirectional"))
    )
    (net (code "215") (name "X0D10{slash}QS_CLK") (class "Default")
      (node (ref "IC11") (pin "7") (pinfunction "2A_7") (pintype "passive"))
      (node (ref "IC18") (pin "28") (pinfunction "X0D10_28") (pintype "bidirectional"))
      (node (ref "X3") (pin "6") (pinfunction "1_6") (pintype "passive"))
    )
    (net (code "216") (name "X0D11{slash}LCD_BR") (class "Default")
      (node (ref "IC1") (pin "4") (pinfunction "CTRL_4") (pintype "input"))
      (node (ref "IC18") (pin "32") (pinfunction "X0D11_32") (pintype "bidirectional"))
      (node (ref "X3") (pin "3") (pinfunction "1_3") (pintype "passive"))
    )
    (net (code "217") (name "XL_DN0") (class "Default")
      (node (ref "IC18") (pin "9") (pinfunction "X0D41_9") (pintype "bidirectional"))
      (node (ref "IC20") (pin "1") (pinfunction "IO1_1") (pintype "bidirectional"))
      (node (ref "X5") (pin "14") (pinfunction "14_14") (pintype "passive"))
    )
    (net (code "218") (name "XL_DN1") (class "Default")
      (node (ref "IC18") (pin "8") (pinfunction "X0D40_8") (pintype "bidirectional"))
      (node (ref "IC20") (pin "2") (pinfunction "IO2_2") (pintype "bidirectional"))
      (node (ref "X5") (pin "18") (pinfunction "18_18") (pintype "passive"))
    )
    (net (code "219") (name "XL_UP0") (class "Default")
      (node (ref "IC20") (pin "5") (pinfunction "IO4_5") (pintype "bidirectional"))
      (node (ref "R27") (pin "2") (pinfunction "2_2") (pintype "passive"))
      (node (ref "X5") (pin "10") (pinfunction "10_10") (pintype "passive"))
    )
    (net (code "220") (name "XL_UP1") (class "Default")
      (node (ref "IC20") (pin "4") (pinfunction "IO3_4") (pintype "bidirectional"))
      (node (ref "R28") (pin "2") (pinfunction "2_2") (pintype "passive"))
      (node (ref "X5") (pin "6") (pinfunction "6_6") (pintype "passive"))
    )
    (net (code "221") (name "unconnected-(IC5-~{Q7{slash}H}-Pad9)") (class "Default")
      (node (ref "IC5") (pin "9") (pinfunction "~{Q7/H}_9") (pintype "output"))
    )
    (net (code "222") (name "unconnected-(IC6-~{MR}-Pad3)") (class "Default")
      (node (ref "IC6") (pin "3") (pinfunction "~{MR}_3") (pintype "passive"))
    )
    (net (code "223") (name "unconnected-(IC7-SIQ-Pad6)") (class "Default")
      (node (ref "IC7") (pin "6") (pinfunction "SIQ_6") (pintype "bidirectional"))
    )
    (net (code "224") (name "unconnected-(IC9A-~{Q}-Pad3)") (class "Default")
      (node (ref "IC9") (pin "3") (pinfunction "~{Q}_3") (pintype "output"))
    )
    (net (code "225") (name "unconnected-(IC10-NC-40-Pad40)") (class "Default")
      (node (ref "IC10") (pin "40") (pinfunction "NC-40_40") (pintype "no_connect"))
    )
    (net (code "226") (name "unconnected-(IC11-4B1-Pad14)") (class "Default")
      (node (ref "IC11") (pin "14") (pinfunction "4B1_14") (pintype "passive"))
    )
    (net (code "227") (name "unconnected-(IC11-4B2-Pad13)") (class "Default")
      (node (ref "IC11") (pin "13") (pinfunction "4B2_13") (pintype "passive"))
    )
    (net (code "228") (name "unconnected-(IC18A-NC-50-Pad50)") (class "Default")
      (node (ref "IC18") (pin "50") (pinfunction "NC-50_50") (pintype "no_connect"))
    )
    (net (code "229") (name "unconnected-(IC18A-NC-65-Pad65)") (class "Default")
      (node (ref "IC18") (pin "65") (pinfunction "NC-65_65") (pintype "no_connect"))
    )
    (net (code "230") (name "unconnected-(IC18D-X1D00-Pad85)") (class "Default")
      (node (ref "IC18") (pin "85") (pinfunction "X1D00_85") (pintype "bidirectional"))
    )
    (net (code "231") (name "unconnected-(IC18D-X1D01-Pad86)") (class "Default")
      (node (ref "IC18") (pin "86") (pinfunction "X1D01_86") (pintype "bidirectional"))
    )
    (net (code "232") (name "unconnected-(IC18D-X1D02-Pad72)") (class "Default")
      (node (ref "IC18") (pin "72") (pinfunction "X1D02_72") (pintype "bidirectional"))
    )
    (net (code "233") (name "unconnected-(IC18D-X1D03-Pad74)") (class "Default")
      (node (ref "IC18") (pin "74") (pinfunction "X1D03_74") (pintype "bidirectional"))
    )
    (net (code "234") (name "unconnected-(IC18D-X1D04-Pad75)") (class "Default")
      (node (ref "IC18") (pin "75") (pinfunction "X1D04_75") (pintype "bidirectional"))
    )
    (net (code "235") (name "unconnected-(IC18D-X1D05-Pad76)") (class "Default")
      (node (ref "IC18") (pin "76") (pinfunction "X1D05_76") (pintype "bidirectional"))
    )
    (net (code "236") (name "unconnected-(IC18D-X1D06-Pad77)") (class "Default")
      (node (ref "IC18") (pin "77") (pinfunction "X1D06_77") (pintype "bidirectional"))
    )
    (net (code "237") (name "unconnected-(IC18D-X1D07-Pad79)") (class "Default")
      (node (ref "IC18") (pin "79") (pinfunction "X1D07_79") (pintype "bidirectional"))
    )
    (net (code "238") (name "unconnected-(IC18D-X1D08-Pad82)") (class "Default")
      (node (ref "IC18") (pin "82") (pinfunction "X1D08_82") (pintype "bidirectional"))
    )
    (net (code "239") (name "unconnected-(IC18D-X1D09-Pad84)") (class "Default")
      (node (ref "IC18") (pin "84") (pinfunction "X1D09_84") (pintype "bidirectional"))
    )
    (net (code "240") (name "unconnected-(IC18D-X1D14-Pad51)") (class "Default")
      (node (ref "IC18") (pin "51") (pinfunction "X1D14_51") (pintype "bidirectional"))
    )
    (net (code "241") (name "unconnected-(IC18D-X1D15-Pad53)") (class "Default")
      (node (ref "IC18") (pin "53") (pinfunction "X1D15_53") (pintype "bidirectional"))
    )
    (net (code "242") (name "unconnected-(IC18D-X1D16-Pad22)") (class "Default")
      (node (ref "IC18") (pin "22") (pinfunction "X1D16_22") (pintype "bidirectional"))
    )
    (net (code "243") (name "unconnected-(IC18D-X1D17-Pad23)") (class "Default")
      (node (ref "IC18") (pin "23") (pinfunction "X1D17_23") (pintype "bidirectional"))
    )
    (net (code "244") (name "unconnected-(IC18D-X1D18-Pad25)") (class "Default")
      (node (ref "IC18") (pin "25") (pinfunction "X1D18_25") (pintype "bidirectional"))
    )
    (net (code "245") (name "unconnected-(IC18D-X1D19-Pad26)") (class "Default")
      (node (ref "IC18") (pin "26") (pinfunction "X1D19_26") (pintype "bidirectional"))
    )
    (net (code "246") (name "unconnected-(IC18D-X1D20-Pad54)") (class "Default")
      (node (ref "IC18") (pin "54") (pinfunction "X1D20_54") (pintype "bidirectional"))
    )
    (net (code "247") (name "unconnected-(IC18D-X1D21-Pad55)") (class "Default")
      (node (ref "IC18") (pin "55") (pinfunction "X1D21_55") (pintype "bidirectional"))
    )
    (net (code "248") (name "unconnected-(IC18D-X1D38-Pad20)") (class "Default")
      (node (ref "IC18") (pin "20") (pinfunction "X1D38_20") (pintype "bidirectional"))
    )
    (net (code "249") (name "unconnected-(IC18D-X1D39-Pad21)") (class "Default")
      (node (ref "IC18") (pin "21") (pinfunction "X1D39_21") (pintype "bidirectional"))
    )
    (net (code "250") (name "unconnected-(IC24-CLK_OUT-Pad25)") (class "Default")
      (node (ref "IC24") (pin "25") (pinfunction "CLK_OUT_25") (pintype "output"))
    )
    (net (code "251") (name "unconnected-(IC24-CRS{slash}CRS_DV{slash}LED_CFG-Pad40)") (class "Default")
      (node (ref "IC24") (pin "40") (pinfunction "CRS/CRS_DV/LED_CFG_40") (pintype "output"))
    )
    (net (code "252") (name "unconnected-(IC24-PHYAD0(COL)-Pad42)") (class "Default")
      (node (ref "IC24") (pin "42") (pinfunction "PHYAD0(COL)_42") (pintype "output"))
    )
    (net (code "253") (name "unconnected-(IC24-PWR_DOWN{slash}INT-Pad7)") (class "Default")
      (node (ref "IC24") (pin "7") (pinfunction "PWR_DOWN/INT_7") (pintype "input"))
    )
    (net (code "254") (name "unconnected-(IC24-TCK-Pad8)") (class "Default")
      (node (ref "IC24") (pin "8") (pinfunction "TCK_8") (pintype "input"))
    )
    (net (code "255") (name "unconnected-(IC24-TDI-Pad12)") (class "Default")
      (node (ref "IC24") (pin "12") (pinfunction "TDI_12") (pintype "input"))
    )
    (net (code "256") (name "unconnected-(IC24-TDO-Pad9)") (class "Default")
      (node (ref "IC24") (pin "9") (pinfunction "TDO_9") (pintype "output"))
    )
    (net (code "257") (name "unconnected-(IC24-TMS-Pad10)") (class "Default")
      (node (ref "IC24") (pin "10") (pinfunction "TMS_10") (pintype "input"))
    )
    (net (code "258") (name "unconnected-(IC24-X2-Pad33)") (class "Default")
      (node (ref "IC24") (pin "33") (pinfunction "X2_33") (pintype "output"))
    )
    (net (code "259") (name "unconnected-(IC24-~{TRST}-Pad11)") (class "Default")
      (node (ref "IC24") (pin "11") (pinfunction "~{TRST}_11") (pintype "input"))
    )
    (net (code "260") (name "unconnected-(IC26-~{Q7{slash}H}-Pad9)") (class "Default")
      (node (ref "IC26") (pin "9") (pinfunction "~{Q7/H}_9") (pintype "output"))
    )
    (net (code "261") (name "unconnected-(IC27-CLKOUT-Pad13)") (class "Default")
      (node (ref "IC27") (pin "13") (pinfunction "CLKOUT_13") (pintype "output"))
    )
    (net (code "262") (name "unconnected-(J2-DAT1-Pad8)") (class "Default")
      (node (ref "J2") (pin "8") (pinfunction "DAT1_8") (pintype "passive"))
    )
    (net (code "263") (name "unconnected-(J2-DAT2-Pad1)") (class "Default")
      (node (ref "J2") (pin "1") (pinfunction "DAT2_1") (pintype "passive"))
    )
    (net (code "264") (name "unconnected-(LCD1-NC1-Pad35)") (class "Default")
      (node (ref "LCD1") (pin "35") (pinfunction "NC1_35") (pintype "no_connect"))
    )
    (net (code "265") (name "unconnected-(R67-Pad2)") (class "Default")
      (node (ref "R67") (pin "2") (pinfunction "2_2") (pintype "passive"))
    )
    (net (code "266") (name "unconnected-(X5-Pad1)") (class "Default")
      (node (ref "X5") (pin "1") (pinfunction "1_1") (pintype "passive"))
    )
    (net (code "267") (name "unconnected-(X5-Pad2)") (class "Default")
      (node (ref "X5") (pin "2") (pinfunction "2_2") (pintype "passive"))
    )
    (net (code "268") (name "unconnected-(X5-Pad3)") (class "Default")
      (node (ref "X5") (pin "3") (pinfunction "3_3") (pintype "passive"))
    )
    (net (code "269") (name "unconnected-(X5-Pad11)") (class "Default")
      (node (ref "X5") (pin "11") (pinfunction "11_11") (pintype "passive"))
    )
    (net (code "270") (name "unconnected-(X5-Pad17)") (class "Default")
      (node (ref "X5") (pin "17") (pinfunction "17_17") (pintype "passive"))
    )
    (net (code "271") (name "unconnected-(X5-Pad19)") (class "Default")
      (node (ref "X5") (pin "19") (pinfunction "19_19") (pintype "passive"))
    )
    (net (code "272") (name "unconnected-(XO1-EN-Pad1)") (class "Default")
      (node (ref "XO1") (pin "1") (pinfunction "EN_1") (pintype "input"))
    )
    (net (code "273") (name "unconnected-(XO2-EN-Pad1)") (class "Default")
      (node (ref "XO2") (pin "1") (pinfunction "EN_1") (pintype "input"))
    )
    (net (code "274") (name "~{AUDIO_SHDN}") (class "Default")
      (node (ref "IC23") (pin "1") (pinfunction "~{SHDN}_1") (pintype "input"))
      (node (ref "IC26") (pin "6") (pinfunction "Q6/G_6") (pintype "output"))
      (node (ref "R37") (pin "1") (pinfunction "1_1") (pintype "passive"))
    )
    (net (code "275") (name "~{QSPI_CS}") (class "Default")
      (node (ref "IC11") (pin "2") (pinfunction "1B1_2") (pintype "passive"))
      (node (ref "IC13") (pin "1") (pinfunction "~{CS}_1") (pintype "input"))
      (node (ref "R14") (pin "2") (pinfunction "2_2") (pintype "passive"))
      (node (ref "X2") (pin "10") (pinfunction "1_10") (pintype "passive"))
    )
    (net (code "276") (name "~{QSPI_SEL}") (class "Default")
      (node (ref "IC11") (pin "1") (pinfunction "S_1") (pintype "input"))
      (node (ref "IC14") (pin "1") (pinfunction "S_1") (pintype "input"))
      (node (ref "X2") (pin "2") (pinfunction "1_2") (pintype "passive"))
      (node (ref "X2") (pin "4") (pinfunction "1_4") (pintype "passive"))
    )
    (net (code "277") (name "~{RESET}") (class "Default")
      (node (ref "IC18") (pin "123") (pinfunction "TRST_N_123") (pintype "passive"))
      (node (ref "IC18") (pin "124") (pinfunction "RST_N_124") (pintype "passive"))
      (node (ref "IC21") (pin "4") (pinfunction "Y_4") (pintype "output"))
      (node (ref "IC28") (pin "18") (pinfunction "~{RESET}_18") (pintype "input"))
      (node (ref "IC8") (pin "1") (pinfunction "~{RESET}_1") (pintype "output"))
      (node (ref "IC9") (pin "6") (pinfunction "~{CLR}_6") (pintype "input"))
      (node (ref "JP1") (pin "1") (pinfunction "1_1") (pintype "passive"))
      (node (ref "R12") (pin "2") (pinfunction "2_2") (pintype "passive"))
    )
    (net (code "278") (name "~{RIVERDI_INT}") (class "Default")
      (node (ref "IC28") (pin "5") (pinfunction "GPB4_5") (pintype "bidirectional"))
      (node (ref "X9") (pin "7") (pinfunction "1_7") (pintype "passive"))
    )
    (net (code "279") (name "~{RIVERDI_PD}") (class "Default")
      (node (ref "IC26") (pin "5") (pinfunction "Q5/F_5") (pintype "output"))
      (node (ref "X9") (pin "8") (pinfunction "1_8") (pintype "passive"))
    )
    (net (code "280") (name "~{RTC_INT}") (class "Default")
      (node (ref "IC27") (pin "5") (pinfunction "~{INT}_5") (pintype "output"))
      (node (ref "IC28") (pin "3") (pinfunction "GPB2_3") (pintype "bidirectional"))
    )
    (net (code "281") (name "~{SD_CAS}") (class "Default")
      (node (ref "IC10") (pin "17") (pinfunction "~{CAS}_17") (pintype "input"))
      (node (ref "IC11") (pin "3") (pinfunction "1B2_3") (pintype "passive"))
      (node (ref "IC12") (pin "1") (pinfunction "A_1") (pintype "input"))
    )
    (net (code "282") (name "~{SD_DETECT}") (class "Default")
      (node (ref "IC28") (pin "6") (pinfunction "GPB5_6") (pintype "bidirectional"))
      (node (ref "J2") (pin "SW1") (pinfunction "SW1_SW1") (pintype "passive"))
    )
    (net (code "283") (name "~{SD_RAS}") (class "Default")
      (node (ref "IC10") (pin "18") (pinfunction "~{RAS}_18") (pintype "input"))
      (node (ref "IC11") (pin "10") (pinfunction "3B2_10") (pintype "passive"))
    )
    (net (code "284") (name "~{SD_WE}") (class "Default")
      (node (ref "IC10") (pin "16") (pinfunction "~{WE}_16") (pintype "input"))
      (node (ref "IC11") (pin "6") (pinfunction "2B2_6") (pintype "passive"))
      (node (ref "IC12") (pin "2") (pinfunction "B_2") (pintype "input"))
    )
    (net (code "285") (name "~{SPI1_EEPROM}") (class "Default")
      (node (ref "IC26") (pin "4") (pinfunction "Q4/E_4") (pintype "output"))
      (node (ref "IC29") (pin "1") (pinfunction "~{CS}_1") (pintype "input"))
    )
    (net (code "286") (name "~{SPI1_IOEXP}") (class "Default")
      (node (ref "IC26") (pin "1") (pinfunction "Q1/B_1") (pintype "output"))
      (node (ref "IC28") (pin "11") (pinfunction "~{CS}_11") (pintype "input"))
    )
    (net (code "287") (name "~{SPI1_RTC}") (class "Default")
      (node (ref "IC26") (pin "15") (pinfunction "Q0/A_15") (pintype "output"))
      (node (ref "IC27") (pin "6") (pinfunction "CE_6") (pintype "input"))
    )
    (net (code "288") (name "~{SPI1_SDCARD}") (class "Default")
      (node (ref "IC26") (pin "3") (pinfunction "Q3/D_3") (pintype "output"))
      (node (ref "J2") (pin "2") (pinfunction "CD/DAT3_2") (pintype "passive"))
    )
    (net (code "289") (name "~{SPI1_TOUCH}") (class "Default")
      (node (ref "IC18") (pin "4") (pinfunction "X0D37_4") (pintype "bidirectional"))
      (node (ref "IC7") (pin "8") (pinfunction "SS_8") (pintype "bidirectional"))
    )
    (net (code "290") (name "~{SPI1_W5500}") (class "Default")
      (node (ref "IC26") (pin "2") (pinfunction "Q2/C_2") (pintype "output"))
      (node (ref "MOD1") (pin "4") (pinfunction "SCS_4") (pintype "input"))
    )
    (net (code "291") (name "~{USB_OC}") (class "Default")
      (node (ref "IC15") (pin "3") (pinfunction "~{OC}_3") (pintype "passive"))
      (node (ref "IC28") (pin "7") (pinfunction "GPB6_7") (pintype "bidirectional"))
      (node (ref "R19") (pin "1") (pinfunction "1_1") (pintype "passive"))
    )
    (net (code "292") (name "~{W5500_INT}") (class "Default")
      (node (ref "IC28") (pin "4") (pinfunction "GPB3_4") (pintype "bidirectional"))
      (node (ref "MOD1") (pin "9") (pinfunction "INT_9") (pintype "passive"))
    )
  )
)
